# A1-A1_Switches_new.net
KiCad netlist of a schematic drawn in Altium Designer
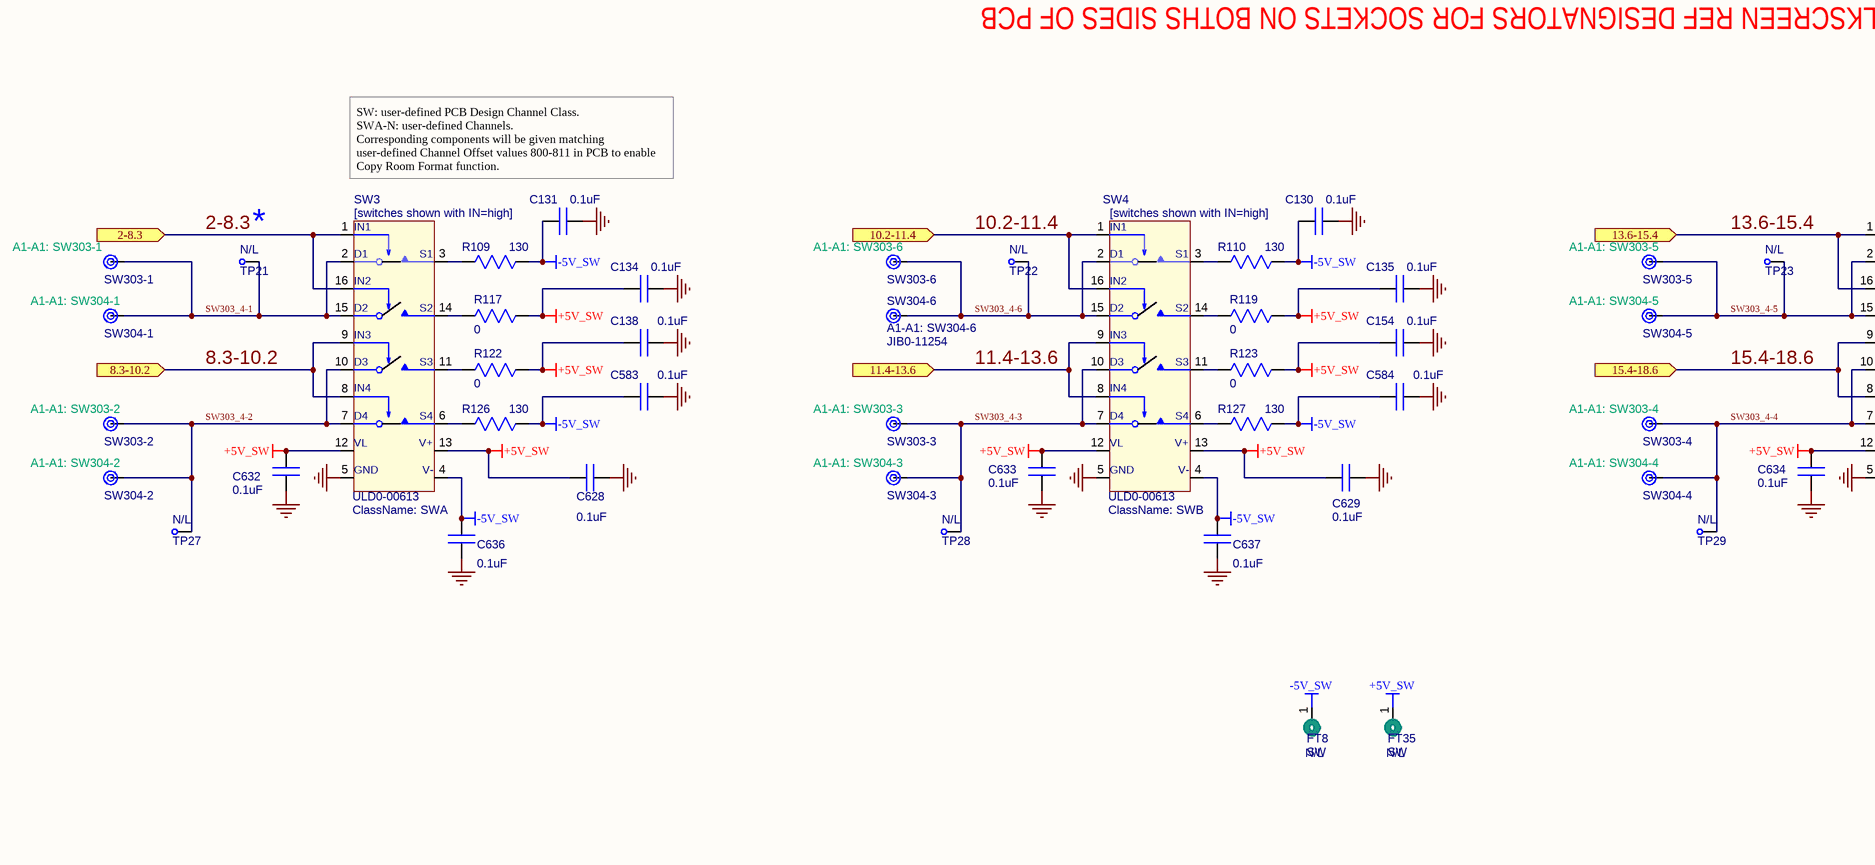
[diagram p0: A1-A1 Switches new.SchDoc, top left]
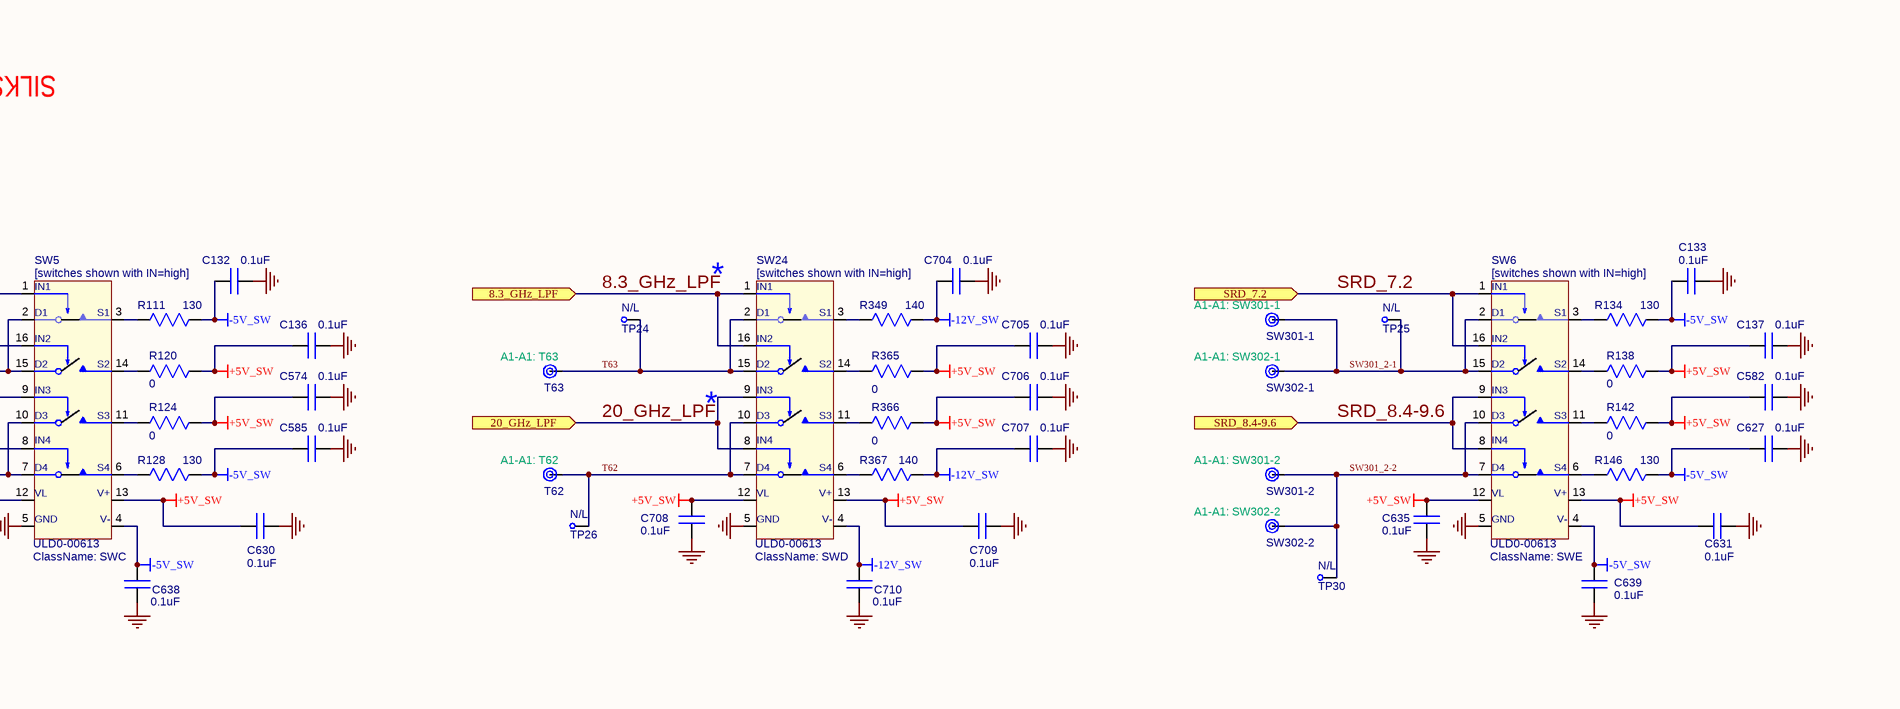
[diagram p1: A1-A1 Switches new.SchDoc, top right]
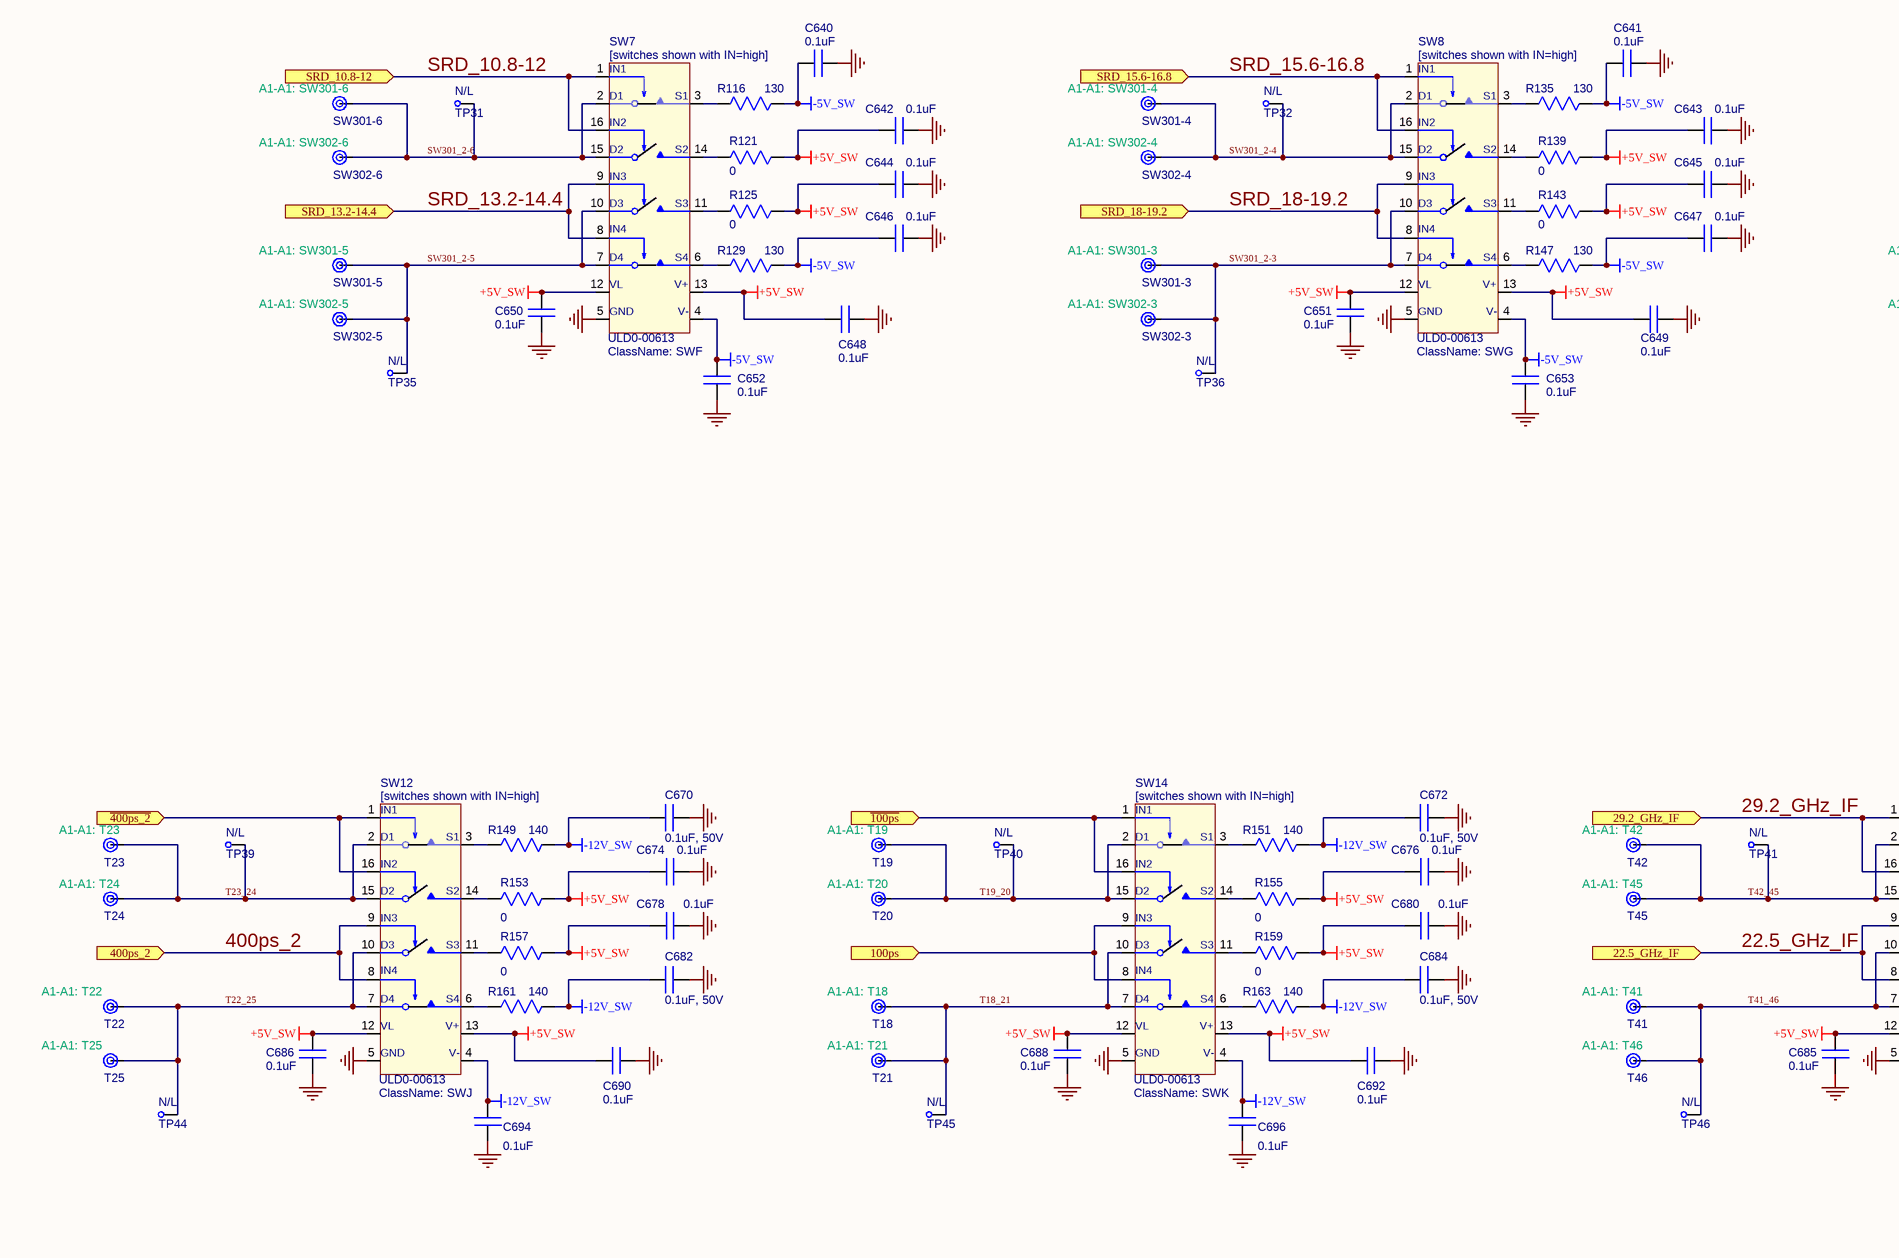
[diagram p2: A1-A1 Switches new.SchDoc, bottom left]
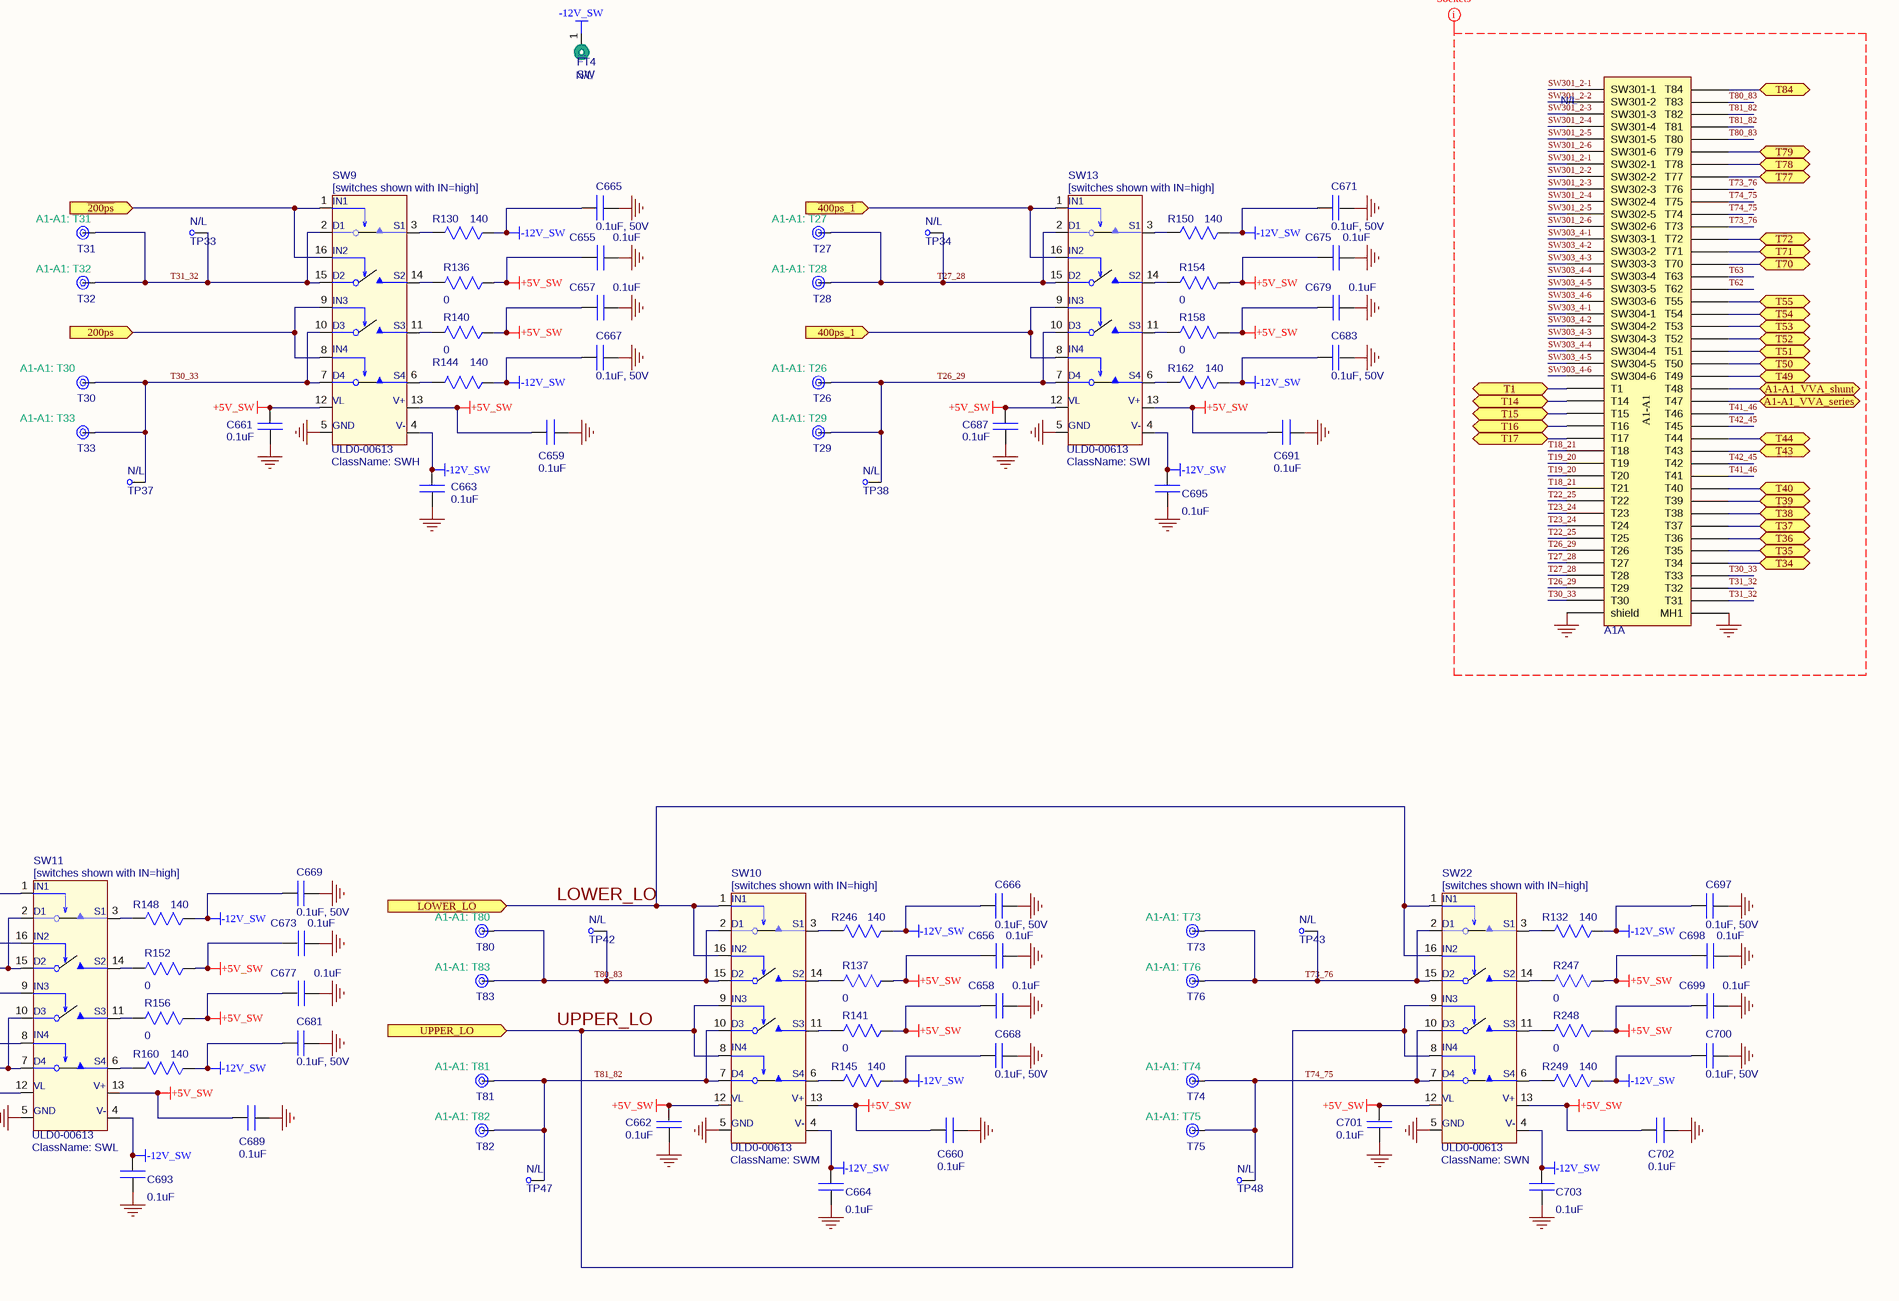
[diagram p3: A1-A1 Switches new.SchDoc, bottom right]

(export (version "E")
  (design (tool "Eeschema 10.0.6"))
  (components
    (comp (ref "A1")
      (value "PCB features")
      (footprint "Hydra_A1_output_modules")
      (description "Hydra A1 output modules (PCB features)")
      (fields (field (name "NOLOAD") "N/L") (field (name "APPROVED") "*"))
      (libsource (lib "Giga-tronics") (part "Hydra A1 output modules"))
    )
    (comp (ref "C130")
      (value "0.1uF")
      (footprint "CAP-0402-N")
      (description ".1 UF,10%;X7R;16V,CHIP;0402")
      (fields (field (name "APPROVED") "CL"))
      (libsource (lib "Giga-tronics") (part "CK40-04100"))
    )
    (comp (ref "C131")
      (value "0.1uF")
      (footprint "CAP-0402-N")
      (description ".1 UF,10%;X7R;16V,CHIP;0402")
      (fields (field (name "APPROVED") "CL"))
      (libsource (lib "Giga-tronics") (part "CK40-04100"))
    )
    (comp (ref "C132")
      (value "0.1uF")
      (footprint "CAP-0402-N")
      (description ".1 UF,10%;X7R;16V,CHIP;0402")
      (fields (field (name "APPROVED") "CL"))
      (libsource (lib "Giga-tronics") (part "CK40-04100"))
    )
    (comp (ref "C133")
      (value "0.1uF")
      (footprint "CAP-0402-N")
      (description ".1 UF,10%;X7R;16V,CHIP;0402")
      (fields (field (name "APPROVED") "CL"))
      (libsource (lib "Giga-tronics") (part "CK40-04100"))
    )
    (comp (ref "C134")
      (value "0.1uF")
      (footprint "CAP-0402-N")
      (description ".1 UF,10%;X7R;16V,CHIP;0402")
      (fields (field (name "APPROVED") "CL"))
      (libsource (lib "Giga-tronics") (part "CK40-04100"))
    )
    (comp (ref "C135")
      (value "0.1uF")
      (footprint "CAP-0402-N")
      (description ".1 UF,10%;X7R;16V,CHIP;0402")
      (fields (field (name "APPROVED") "CL"))
      (libsource (lib "Giga-tronics") (part "CK40-04100"))
    )
    (comp (ref "C136")
      (value "0.1uF")
      (footprint "CAP-0402-N")
      (description ".1 UF,10%;X7R;16V,CHIP;0402")
      (fields (field (name "APPROVED") "CL"))
      (libsource (lib "Giga-tronics") (part "CK40-04100"))
    )
    (comp (ref "C137")
      (value "0.1uF")
      (footprint "CAP-0402-N")
      (description ".1 UF,10%;X7R;16V,CHIP;0402")
      (fields (field (name "APPROVED") "CL"))
      (libsource (lib "Giga-tronics") (part "CK40-04100"))
    )
    (comp (ref "C138")
      (value "0.1uF")
      (footprint "CAP-0402-N")
      (description ".1 UF,10%;X7R;16V,CHIP;0402")
      (fields (field (name "APPROVED") "CL"))
      (libsource (lib "Giga-tronics") (part "CK40-04100"))
    )
    (comp (ref "C154")
      (value "0.1uF")
      (footprint "CAP-0402-N")
      (description ".1 UF,10%;X7R;16V,CHIP;0402")
      (fields (field (name "APPROVED") "CL"))
      (libsource (lib "Giga-tronics") (part "CK40-04100"))
    )
    (comp (ref "C574")
      (value "0.1uF")
      (footprint "CAP-0402-N")
      (description ".1 UF,10%;X7R;16V,CHIP;0402")
      (fields (field (name "APPROVED") "CL"))
      (libsource (lib "Giga-tronics") (part "CK40-04100"))
    )
    (comp (ref "C582")
      (value "0.1uF")
      (footprint "CAP-0402-N")
      (description ".1 UF,10%;X7R;16V,CHIP;0402")
      (fields (field (name "APPROVED") "CL"))
      (libsource (lib "Giga-tronics") (part "CK40-04100"))
    )
    (comp (ref "C583")
      (value "0.1uF")
      (footprint "CAP-0402-N")
      (description ".1 UF,10%;X7R;16V,CHIP;0402")
      (fields (field (name "APPROVED") "CL"))
      (libsource (lib "Giga-tronics") (part "CK40-04100"))
    )
    (comp (ref "C584")
      (value "0.1uF")
      (footprint "CAP-0402-N")
      (description ".1 UF,10%;X7R;16V,CHIP;0402")
      (fields (field (name "APPROVED") "CL"))
      (libsource (lib "Giga-tronics") (part "CK40-04100"))
    )
    (comp (ref "C585")
      (value "0.1uF")
      (footprint "CAP-0402-N")
      (description ".1 UF,10%;X7R;16V,CHIP;0402")
      (fields (field (name "APPROVED") "CL"))
      (libsource (lib "Giga-tronics") (part "CK40-04100"))
    )
    (comp (ref "C627")
      (value "0.1uF")
      (footprint "CAP-0402-N")
      (description ".1 UF,10%;X7R;16V,CHIP;0402")
      (fields (field (name "APPROVED") "CL"))
      (libsource (lib "Giga-tronics") (part "CK40-04100"))
    )
    (comp (ref "C628")
      (value "0.1uF")
      (footprint "CAP-0402-N")
      (description ".1 UF,10%;X7R;16V,CHIP;0402")
      (fields (field (name "APPROVED") "CL"))
      (libsource (lib "Giga-tronics") (part "CK40-04100"))
    )
    (comp (ref "C629")
      (value "0.1uF")
      (footprint "CAP-0402-N")
      (description ".1 UF,10%;X7R;16V,CHIP;0402")
      (fields (field (name "APPROVED") "CL"))
      (libsource (lib "Giga-tronics") (part "CK40-04100"))
    )
    (comp (ref "C630")
      (value "0.1uF")
      (footprint "CAP-0402-N")
      (description ".1 UF,10%;X7R;16V,CHIP;0402")
      (fields (field (name "APPROVED") "CL"))
      (libsource (lib "Giga-tronics") (part "CK40-04100"))
    )
    (comp (ref "C631")
      (value "0.1uF")
      (footprint "CAP-0402-N")
      (description ".1 UF,10%;X7R;16V,CHIP;0402")
      (fields (field (name "APPROVED") "CL"))
      (libsource (lib "Giga-tronics") (part "CK40-04100"))
    )
    (comp (ref "C632")
      (value "0.1uF")
      (footprint "CAP-0402-N")
      (description ".1 UF,10%;X7R;16V,CHIP;0402")
      (fields (field (name "APPROVED") "CL"))
      (libsource (lib "Giga-tronics") (part "CK40-04100"))
    )
    (comp (ref "C633")
      (value "0.1uF")
      (footprint "CAP-0402-N")
      (description ".1 UF,10%;X7R;16V,CHIP;0402")
      (fields (field (name "APPROVED") "CL"))
      (libsource (lib "Giga-tronics") (part "CK40-04100"))
    )
    (comp (ref "C634")
      (value "0.1uF")
      (footprint "CAP-0402-N")
      (description ".1 UF,10%;X7R;16V,CHIP;0402")
      (fields (field (name "APPROVED") "CL"))
      (libsource (lib "Giga-tronics") (part "CK40-04100"))
    )
    (comp (ref "C635")
      (value "0.1uF")
      (footprint "CAP-0402-N")
      (description ".1 UF,10%;X7R;16V,CHIP;0402")
      (fields (field (name "APPROVED") "CL"))
      (libsource (lib "Giga-tronics") (part "CK40-04100"))
    )
    (comp (ref "C636")
      (value "0.1uF")
      (footprint "CAP-0402-N")
      (description ".1 UF,10%;X7R;16V,CHIP;0402")
      (fields (field (name "APPROVED") "CL"))
      (libsource (lib "Giga-tronics") (part "CK40-04100"))
    )
    (comp (ref "C637")
      (value "0.1uF")
      (footprint "CAP-0402-N")
      (description ".1 UF,10%;X7R;16V,CHIP;0402")
      (fields (field (name "APPROVED") "CL"))
      (libsource (lib "Giga-tronics") (part "CK40-04100"))
    )
    (comp (ref "C638")
      (value "0.1uF")
      (footprint "CAP-0402-N")
      (description ".1 UF,10%;X7R;16V,CHIP;0402")
      (fields (field (name "APPROVED") "CL"))
      (libsource (lib "Giga-tronics") (part "CK40-04100"))
    )
    (comp (ref "C639")
      (value "0.1uF")
      (footprint "CAP-0402-N")
      (description ".1 UF,10%;X7R;16V,CHIP;0402")
      (fields (field (name "APPROVED") "CL"))
      (libsource (lib "Giga-tronics") (part "CK40-04100"))
    )
    (comp (ref "C640")
      (value "0.1uF")
      (footprint "CAP-0402-N")
      (description ".1 UF,10%;X7R;16V,CHIP;0402")
      (fields (field (name "APPROVED") "CL"))
      (libsource (lib "Giga-tronics") (part "CK40-04100"))
    )
    (comp (ref "C641")
      (value "0.1uF")
      (footprint "CAP-0402-N")
      (description ".1 UF,10%;X7R;16V,CHIP;0402")
      (fields (field (name "APPROVED") "CL"))
      (libsource (lib "Giga-tronics") (part "CK40-04100"))
    )
    (comp (ref "C642")
      (value "0.1uF")
      (footprint "CAP-0402-N")
      (description ".1 UF,10%;X7R;16V,CHIP;0402")
      (fields (field (name "APPROVED") "CL"))
      (libsource (lib "Giga-tronics") (part "CK40-04100"))
    )
    (comp (ref "C643")
      (value "0.1uF")
      (footprint "CAP-0402-N")
      (description ".1 UF,10%;X7R;16V,CHIP;0402")
      (fields (field (name "APPROVED") "CL"))
      (libsource (lib "Giga-tronics") (part "CK40-04100"))
    )
    (comp (ref "C644")
      (value "0.1uF")
      (footprint "CAP-0402-N")
      (description ".1 UF,10%;X7R;16V,CHIP;0402")
      (fields (field (name "APPROVED") "CL"))
      (libsource (lib "Giga-tronics") (part "CK40-04100"))
    )
    (comp (ref "C645")
      (value "0.1uF")
      (footprint "CAP-0402-N")
      (description ".1 UF,10%;X7R;16V,CHIP;0402")
      (fields (field (name "APPROVED") "CL"))
      (libsource (lib "Giga-tronics") (part "CK40-04100"))
    )
    (comp (ref "C646")
      (value "0.1uF")
      (footprint "CAP-0402-N")
      (description ".1 UF,10%;X7R;16V,CHIP;0402")
      (fields (field (name "APPROVED") "CL"))
      (libsource (lib "Giga-tronics") (part "CK40-04100"))
    )
    (comp (ref "C647")
      (value "0.1uF")
      (footprint "CAP-0402-N")
      (description ".1 UF,10%;X7R;16V,CHIP;0402")
      (fields (field (name "APPROVED") "CL"))
      (libsource (lib "Giga-tronics") (part "CK40-04100"))
    )
    (comp (ref "C648")
      (value "0.1uF")
      (footprint "CAP-0402-N")
      (description ".1 UF,10%;X7R;16V,CHIP;0402")
      (fields (field (name "APPROVED") "CL"))
      (libsource (lib "Giga-tronics") (part "CK40-04100"))
    )
    (comp (ref "C649")
      (value "0.1uF")
      (footprint "CAP-0402-N")
      (description ".1 UF,10%;X7R;16V,CHIP;0402")
      (fields (field (name "APPROVED") "CL"))
      (libsource (lib "Giga-tronics") (part "CK40-04100"))
    )
    (comp (ref "C650")
      (value "0.1uF")
      (footprint "CAP-0402-N")
      (description ".1 UF,10%;X7R;16V,CHIP;0402")
      (fields (field (name "APPROVED") "CL"))
      (libsource (lib "Giga-tronics") (part "CK40-04100"))
    )
    (comp (ref "C651")
      (value "0.1uF")
      (footprint "CAP-0402-N")
      (description ".1 UF,10%;X7R;16V,CHIP;0402")
      (fields (field (name "APPROVED") "CL"))
      (libsource (lib "Giga-tronics") (part "CK40-04100"))
    )
    (comp (ref "C652")
      (value "0.1uF")
      (footprint "CAP-0402-N")
      (description ".1 UF,10%;X7R;16V,CHIP;0402")
      (fields (field (name "APPROVED") "CL"))
      (libsource (lib "Giga-tronics") (part "CK40-04100"))
    )
    (comp (ref "C653")
      (value "0.1uF")
      (footprint "CAP-0402-N")
      (description ".1 UF,10%;X7R;16V,CHIP;0402")
      (fields (field (name "APPROVED") "CL"))
      (libsource (lib "Giga-tronics") (part "CK40-04100"))
    )
    (comp (ref "C655")
      (value "0.1uF")
      (footprint "CAP-0402-N")
      (description ".1 UF,10%;X7R;16V,CHIP;0402")
      (fields (field (name "APPROVED") "CL"))
      (libsource (lib "Giga-tronics") (part "CK40-04100"))
    )
    (comp (ref "C656")
      (value "0.1uF")
      (footprint "CAP-0402-N")
      (description ".1 UF,10%;X7R;16V,CHIP;0402")
      (fields (field (name "APPROVED") "CL"))
      (libsource (lib "Giga-tronics") (part "CK40-04100"))
    )
    (comp (ref "C657")
      (value "0.1uF")
      (footprint "CAP-0402-N")
      (description ".1 UF,10%;X7R;16V,CHIP;0402")
      (fields (field (name "APPROVED") "CL"))
      (libsource (lib "Giga-tronics") (part "CK40-04100"))
    )
    (comp (ref "C658")
      (value "0.1uF")
      (footprint "CAP-0402-N")
      (description ".1 UF,10%;X7R;16V,CHIP;0402")
      (fields (field (name "APPROVED") "CL"))
      (libsource (lib "Giga-tronics") (part "CK40-04100"))
    )
    (comp (ref "C659")
      (value "0.1uF")
      (footprint "CAP-0402-N")
      (description ".1 UF,10%;X7R;16V,CHIP;0402")
      (fields (field (name "APPROVED") "CL"))
      (libsource (lib "Giga-tronics") (part "CK40-04100"))
    )
    (comp (ref "C660")
      (value "0.1uF")
      (footprint "CAP-0402-N")
      (description ".1 UF,10%;X7R;16V,CHIP;0402")
      (fields (field (name "APPROVED") "CL"))
      (libsource (lib "Giga-tronics") (part "CK40-04100"))
    )
    (comp (ref "C661")
      (value "0.1uF")
      (footprint "CAP-0402-N")
      (description ".1 UF,10%;X7R;16V,CHIP;0402")
      (fields (field (name "APPROVED") "CL"))
      (libsource (lib "Giga-tronics") (part "CK40-04100"))
    )
    (comp (ref "C662")
      (value "0.1uF")
      (footprint "CAP-0402-N")
      (description ".1 UF,10%;X7R;16V,CHIP;0402")
      (fields (field (name "APPROVED") "CL"))
      (libsource (lib "Giga-tronics") (part "CK40-04100"))
    )
    (comp (ref "C663")
      (value "0.1uF")
      (footprint "CAP-0402-N")
      (description ".1 UF,10%;X7R;16V,CHIP;0402")
      (fields (field (name "APPROVED") "CL"))
      (libsource (lib "Giga-tronics") (part "CK40-04100"))
    )
    (comp (ref "C664")
      (value "0.1uF")
      (footprint "CAP-0402-N")
      (description ".1 UF,10%;X7R;16V,CHIP;0402")
      (fields (field (name "APPROVED") "CL"))
      (libsource (lib "Giga-tronics") (part "CK40-04100"))
    )
    (comp (ref "C665")
      (value "0.1uF, 50V")
      (footprint "CAP-0603-N")
      (description ".1UF;5%;X7R;50V;CHIP;0603")
      (fields (field (name "APPROVED") "CL"))
      (libsource (lib "Giga-tronics") (part "CK45-14100"))
    )
    (comp (ref "C666")
      (value "0.1uF, 50V")
      (footprint "CAP-0603-N")
      (description ".1UF;5%;X7R;50V;CHIP;0603")
      (fields (field (name "APPROVED") "CL"))
      (libsource (lib "Giga-tronics") (part "CK45-14100"))
    )
    (comp (ref "C667")
      (value "0.1uF, 50V")
      (footprint "CAP-0603-N")
      (description ".1UF;5%;X7R;50V;CHIP;0603")
      (fields (field (name "APPROVED") "CL"))
      (libsource (lib "Giga-tronics") (part "CK45-14100"))
    )
    (comp (ref "C668")
      (value "0.1uF, 50V")
      (footprint "CAP-0603-N")
      (description ".1UF;5%;X7R;50V;CHIP;0603")
      (fields (field (name "APPROVED") "CL"))
      (libsource (lib "Giga-tronics") (part "CK45-14100"))
    )
    (comp (ref "C669")
      (value "0.1uF, 50V")
      (footprint "CAP-0603-N")
      (description ".1UF;5%;X7R;50V;CHIP;0603")
      (fields (field (name "APPROVED") "CL"))
      (libsource (lib "Giga-tronics") (part "CK45-14100"))
    )
    (comp (ref "C670")
      (value "0.1uF, 50V")
      (footprint "CAP-0603-N")
      (description ".1UF;5%;X7R;50V;CHIP;0603")
      (fields (field (name "APPROVED") "CL"))
      (libsource (lib "Giga-tronics") (part "CK45-14100"))
    )
    (comp (ref "C671")
      (value "0.1uF, 50V")
      (footprint "CAP-0603-N")
      (description ".1UF;5%;X7R;50V;CHIP;0603")
      (fields (field (name "APPROVED") "CL"))
      (libsource (lib "Giga-tronics") (part "CK45-14100"))
    )
    (comp (ref "C672")
      (value "0.1uF, 50V")
      (footprint "CAP-0603-N")
      (description ".1UF;5%;X7R;50V;CHIP;0603")
      (fields (field (name "APPROVED") "CL"))
      (libsource (lib "Giga-tronics") (part "CK45-14100"))
    )
    (comp (ref "C673")
      (value "0.1uF")
      (footprint "CAP-0402-N")
      (description ".1 UF,10%;X7R;16V,CHIP;0402")
      (fields (field (name "APPROVED") "CL"))
      (libsource (lib "Giga-tronics") (part "CK40-04100"))
    )
    (comp (ref "C674")
      (value "0.1uF")
      (footprint "CAP-0402-N")
      (description ".1 UF,10%;X7R;16V,CHIP;0402")
      (fields (field (name "APPROVED") "CL"))
      (libsource (lib "Giga-tronics") (part "CK40-04100"))
    )
    (comp (ref "C675")
      (value "0.1uF")
      (footprint "CAP-0402-N")
      (description ".1 UF,10%;X7R;16V,CHIP;0402")
      (fields (field (name "APPROVED") "CL"))
      (libsource (lib "Giga-tronics") (part "CK40-04100"))
    )
    (comp (ref "C676")
      (value "0.1uF")
      (footprint "CAP-0402-N")
      (description ".1 UF,10%;X7R;16V,CHIP;0402")
      (fields (field (name "APPROVED") "CL"))
      (libsource (lib "Giga-tronics") (part "CK40-04100"))
    )
    (comp (ref "C677")
      (value "0.1uF")
      (footprint "CAP-0402-N")
      (description ".1 UF,10%;X7R;16V,CHIP;0402")
      (fields (field (name "APPROVED") "CL"))
      (libsource (lib "Giga-tronics") (part "CK40-04100"))
    )
    (comp (ref "C678")
      (value "0.1uF")
      (footprint "CAP-0402-N")
      (description ".1 UF,10%;X7R;16V,CHIP;0402")
      (fields (field (name "APPROVED") "CL"))
      (libsource (lib "Giga-tronics") (part "CK40-04100"))
    )
    (comp (ref "C679")
      (value "0.1uF")
      (footprint "CAP-0402-N")
      (description ".1 UF,10%;X7R;16V,CHIP;0402")
      (fields (field (name "APPROVED") "CL"))
      (libsource (lib "Giga-tronics") (part "CK40-04100"))
    )
    (comp (ref "C680")
      (value "0.1uF")
      (footprint "CAP-0402-N")
      (description ".1 UF,10%;X7R;16V,CHIP;0402")
      (fields (field (name "APPROVED") "CL"))
      (libsource (lib "Giga-tronics") (part "CK40-04100"))
    )
    (comp (ref "C681")
      (value "0.1uF, 50V")
      (footprint "CAP-0603-N")
      (description ".1UF;5%;X7R;50V;CHIP;0603")
      (fields (field (name "APPROVED") "CL"))
      (libsource (lib "Giga-tronics") (part "CK45-14100"))
    )
    (comp (ref "C682")
      (value "0.1uF, 50V")
      (footprint "CAP-0603-N")
      (description ".1UF;5%;X7R;50V;CHIP;0603")
      (fields (field (name "APPROVED") "CL"))
      (libsource (lib "Giga-tronics") (part "CK45-14100"))
    )
    (comp (ref "C683")
      (value "0.1uF, 50V")
      (footprint "CAP-0603-N")
      (description ".1UF;5%;X7R;50V;CHIP;0603")
      (fields (field (name "APPROVED") "CL"))
      (libsource (lib "Giga-tronics") (part "CK45-14100"))
    )
    (comp (ref "C684")
      (value "0.1uF, 50V")
      (footprint "CAP-0603-N")
      (description ".1UF;5%;X7R;50V;CHIP;0603")
      (fields (field (name "APPROVED") "CL"))
      (libsource (lib "Giga-tronics") (part "CK45-14100"))
    )
    (comp (ref "C685")
      (value "0.1uF")
      (footprint "CAP-0402-N")
      (description ".1 UF,10%;X7R;16V,CHIP;0402")
      (fields (field (name "APPROVED") "CL"))
      (libsource (lib "Giga-tronics") (part "CK40-04100"))
    )
    (comp (ref "C686")
      (value "0.1uF")
      (footprint "CAP-0402-N")
      (description ".1 UF,10%;X7R;16V,CHIP;0402")
      (fields (field (name "APPROVED") "CL"))
      (libsource (lib "Giga-tronics") (part "CK40-04100"))
    )
    (comp (ref "C687")
      (value "0.1uF")
      (footprint "CAP-0402-N")
      (description ".1 UF,10%;X7R;16V,CHIP;0402")
      (fields (field (name "APPROVED") "CL"))
      (libsource (lib "Giga-tronics") (part "CK40-04100"))
    )
    (comp (ref "C688")
      (value "0.1uF")
      (footprint "CAP-0402-N")
      (description ".1 UF,10%;X7R;16V,CHIP;0402")
      (fields (field (name "APPROVED") "CL"))
      (libsource (lib "Giga-tronics") (part "CK40-04100"))
    )
    (comp (ref "C689")
      (value "0.1uF")
      (footprint "CAP-0402-N")
      (description ".1 UF,10%;X7R;16V,CHIP;0402")
      (fields (field (name "APPROVED") "CL"))
      (libsource (lib "Giga-tronics") (part "CK40-04100"))
    )
    (comp (ref "C690")
      (value "0.1uF")
      (footprint "CAP-0402-N")
      (description ".1 UF,10%;X7R;16V,CHIP;0402")
      (fields (field (name "APPROVED") "CL"))
      (libsource (lib "Giga-tronics") (part "CK40-04100"))
    )
    (comp (ref "C691")
      (value "0.1uF")
      (footprint "CAP-0402-N")
      (description ".1 UF,10%;X7R;16V,CHIP;0402")
      (fields (field (name "APPROVED") "CL"))
      (libsource (lib "Giga-tronics") (part "CK40-04100"))
    )
    (comp (ref "C692")
      (value "0.1uF")
      (footprint "CAP-0402-N")
      (description ".1 UF,10%;X7R;16V,CHIP;0402")
      (fields (field (name "APPROVED") "CL"))
      (libsource (lib "Giga-tronics") (part "CK40-04100"))
    )
    (comp (ref "C693")
      (value "0.1uF")
      (footprint "CAP-0402-N")
      (description ".1 UF,10%;X7R;16V,CHIP;0402")
      (fields (field (name "APPROVED") "CL"))
      (libsource (lib "Giga-tronics") (part "CK40-04100"))
    )
    (comp (ref "C694")
      (value "0.1uF")
      (footprint "CAP-0402-N")
      (description ".1 UF,10%;X7R;16V,CHIP;0402")
      (fields (field (name "APPROVED") "CL"))
      (libsource (lib "Giga-tronics") (part "CK40-04100"))
    )
    (comp (ref "C695")
      (value "0.1uF")
      (footprint "CAP-0402-N")
      (description ".1 UF,10%;X7R;16V,CHIP;0402")
      (fields (field (name "APPROVED") "CL"))
      (libsource (lib "Giga-tronics") (part "CK40-04100"))
    )
    (comp (ref "C696")
      (value "0.1uF")
      (footprint "CAP-0402-N")
      (description ".1 UF,10%;X7R;16V,CHIP;0402")
      (fields (field (name "APPROVED") "CL"))
      (libsource (lib "Giga-tronics") (part "CK40-04100"))
    )
    (comp (ref "C697")
      (value "0.1uF, 50V")
      (footprint "CAP-0603-N")
      (description ".1UF;5%;X7R;50V;CHIP;0603")
      (fields (field (name "APPROVED") "CL"))
      (libsource (lib "Giga-tronics") (part "CK45-14100"))
    )
    (comp (ref "C698")
      (value "0.1uF")
      (footprint "CAP-0402-N")
      (description ".1 UF,10%;X7R;16V,CHIP;0402")
      (fields (field (name "APPROVED") "CL"))
      (libsource (lib "Giga-tronics") (part "CK40-04100"))
    )
    (comp (ref "C699")
      (value "0.1uF")
      (footprint "CAP-0402-N")
      (description ".1 UF,10%;X7R;16V,CHIP;0402")
      (fields (field (name "APPROVED") "CL"))
      (libsource (lib "Giga-tronics") (part "CK40-04100"))
    )
    (comp (ref "C700")
      (value "0.1uF, 50V")
      (footprint "CAP-0603-N")
      (description ".1UF;5%;X7R;50V;CHIP;0603")
      (fields (field (name "APPROVED") "CL"))
      (libsource (lib "Giga-tronics") (part "CK45-14100"))
    )
    (comp (ref "C701")
      (value "0.1uF")
      (footprint "CAP-0402-N")
      (description ".1 UF,10%;X7R;16V,CHIP;0402")
      (fields (field (name "APPROVED") "CL"))
      (libsource (lib "Giga-tronics") (part "CK40-04100"))
    )
    (comp (ref "C702")
      (value "0.1uF")
      (footprint "CAP-0402-N")
      (description ".1 UF,10%;X7R;16V,CHIP;0402")
      (fields (field (name "APPROVED") "CL"))
      (libsource (lib "Giga-tronics") (part "CK40-04100"))
    )
    (comp (ref "C703")
      (value "0.1uF")
      (footprint "CAP-0402-N")
      (description ".1 UF,10%;X7R;16V,CHIP;0402")
      (fields (field (name "APPROVED") "CL"))
      (libsource (lib "Giga-tronics") (part "CK40-04100"))
    )
    (comp (ref "C704")
      (value "0.1uF")
      (footprint "CAP-0402-N")
      (description ".1 UF,10%;X7R;16V,CHIP;0402")
      (fields (field (name "APPROVED") "CL"))
      (libsource (lib "Giga-tronics") (part "CK40-04100"))
    )
    (comp (ref "C705")
      (value "0.1uF")
      (footprint "CAP-0402-N")
      (description ".1 UF,10%;X7R;16V,CHIP;0402")
      (fields (field (name "APPROVED") "CL"))
      (libsource (lib "Giga-tronics") (part "CK40-04100"))
    )
    (comp (ref "C706")
      (value "0.1uF")
      (footprint "CAP-0402-N")
      (description ".1 UF,10%;X7R;16V,CHIP;0402")
      (fields (field (name "APPROVED") "CL"))
      (libsource (lib "Giga-tronics") (part "CK40-04100"))
    )
    (comp (ref "C707")
      (value "0.1uF")
      (footprint "CAP-0402-N")
      (description ".1 UF,10%;X7R;16V,CHIP;0402")
      (fields (field (name "APPROVED") "CL"))
      (libsource (lib "Giga-tronics") (part "CK40-04100"))
    )
    (comp (ref "C708")
      (value "0.1uF")
      (footprint "CAP-0402-N")
      (description ".1 UF,10%;X7R;16V,CHIP;0402")
      (fields (field (name "APPROVED") "CL"))
      (libsource (lib "Giga-tronics") (part "CK40-04100"))
    )
    (comp (ref "C709")
      (value "0.1uF")
      (footprint "CAP-0402-N")
      (description ".1 UF,10%;X7R;16V,CHIP;0402")
      (fields (field (name "APPROVED") "CL"))
      (libsource (lib "Giga-tronics") (part "CK40-04100"))
    )
    (comp (ref "C710")
      (value "0.1uF")
      (footprint "CAP-0402-N")
      (description ".1 UF,10%;X7R;16V,CHIP;0402")
      (fields (field (name "APPROVED") "CL"))
      (libsource (lib "Giga-tronics") (part "CK40-04100"))
    )
    (comp (ref "FT4")
      (value "SW")
      (footprint "FromToNode_ML2")
      (fields (field (name "NOLOAD") "N/L") (field (name "APPROVED") "*"))
      (libsource (lib "Giga-tronics") (part "FromToNode"))
    )
    (comp (ref "FT8")
      (value "SW")
      (footprint "FromToNode_ML2")
      (fields (field (name "NOLOAD") "N/L") (field (name "APPROVED") "*"))
      (libsource (lib "Giga-tronics") (part "FromToNode"))
    )
    (comp (ref "FT35")
      (value "SW")
      (footprint "FromToNode_ML2")
      (fields (field (name "NOLOAD") "N/L") (field (name "APPROVED") "*"))
      (libsource (lib "Giga-tronics") (part "FromToNode"))
    )
    (comp (ref "R109")
      (value "130")
      (footprint "RES-0603-N")
      (description "130 OHMS;.1W;1%;200PPM;FILM;CHIP;0603")
      (fields (field (name "APPROVED") "CL"))
      (libsource (lib "Giga-tronics") (part "RK40-01300"))
    )
    (comp (ref "R110")
      (value "130")
      (footprint "RES-0603-N")
      (description "130 OHMS;.1W;1%;200PPM;FILM;CHIP;0603")
      (fields (field (name "APPROVED") "CL"))
      (libsource (lib "Giga-tronics") (part "RK40-01300"))
    )
    (comp (ref "R111")
      (value "130")
      (footprint "RES-0603-N")
      (description "130 OHMS;.1W;1%;200PPM;FILM;CHIP;0603")
      (fields (field (name "APPROVED") "CL"))
      (libsource (lib "Giga-tronics") (part "RK40-01300"))
    )
    (comp (ref "R116")
      (value "130")
      (footprint "RES-0603-N")
      (description "130 OHMS;.1W;1%;200PPM;FILM;CHIP;0603")
      (fields (field (name "APPROVED") "CL"))
      (libsource (lib "Giga-tronics") (part "RK40-01300"))
    )
    (comp (ref "R117")
      (value "0")
      (footprint "RES-0603-N")
      (description "JUMPER;.05 OHMS MAX;1A MAX;0603")
      (fields (field (name "APPROVED") "CL"))
      (libsource (lib "Giga-tronics") (part "RK40-00000"))
    )
    (comp (ref "R119")
      (value "0")
      (footprint "RES-0603-N")
      (description "JUMPER;.05 OHMS MAX;1A MAX;0603")
      (fields (field (name "APPROVED") "CL"))
      (libsource (lib "Giga-tronics") (part "RK40-00000"))
    )
    (comp (ref "R120")
      (value "0")
      (footprint "RES-0603-N")
      (description "JUMPER;.05 OHMS MAX;1A MAX;0603")
      (fields (field (name "APPROVED") "CL"))
      (libsource (lib "Giga-tronics") (part "RK40-00000"))
    )
    (comp (ref "R121")
      (value "0")
      (footprint "RES-0603-N")
      (description "JUMPER;.05 OHMS MAX;1A MAX;0603")
      (fields (field (name "APPROVED") "CL"))
      (libsource (lib "Giga-tronics") (part "RK40-00000"))
    )
    (comp (ref "R122")
      (value "0")
      (footprint "RES-0603-N")
      (description "JUMPER;.05 OHMS MAX;1A MAX;0603")
      (fields (field (name "APPROVED") "CL"))
      (libsource (lib "Giga-tronics") (part "RK40-00000"))
    )
    (comp (ref "R123")
      (value "0")
      (footprint "RES-0603-N")
      (description "JUMPER;.05 OHMS MAX;1A MAX;0603")
      (fields (field (name "APPROVED") "CL"))
      (libsource (lib "Giga-tronics") (part "RK40-00000"))
    )
    (comp (ref "R124")
      (value "0")
      (footprint "RES-0603-N")
      (description "JUMPER;.05 OHMS MAX;1A MAX;0603")
      (fields (field (name "APPROVED") "CL"))
      (libsource (lib "Giga-tronics") (part "RK40-00000"))
    )
    (comp (ref "R125")
      (value "0")
      (footprint "RES-0603-N")
      (description "JUMPER;.05 OHMS MAX;1A MAX;0603")
      (fields (field (name "APPROVED") "CL"))
      (libsource (lib "Giga-tronics") (part "RK40-00000"))
    )
    (comp (ref "R126")
      (value "130")
      (footprint "RES-0603-N")
      (description "130 OHMS;.1W;1%;200PPM;FILM;CHIP;0603")
      (fields (field (name "APPROVED") "CL"))
      (libsource (lib "Giga-tronics") (part "RK40-01300"))
    )
    (comp (ref "R127")
      (value "130")
      (footprint "RES-0603-N")
      (description "130 OHMS;.1W;1%;200PPM;FILM;CHIP;0603")
      (fields (field (name "APPROVED") "CL"))
      (libsource (lib "Giga-tronics") (part "RK40-01300"))
    )
    (comp (ref "R128")
      (value "130")
      (footprint "RES-0603-N")
      (description "130 OHMS;.1W;1%;200PPM;FILM;CHIP;0603")
      (fields (field (name "APPROVED") "CL"))
      (libsource (lib "Giga-tronics") (part "RK40-01300"))
    )
    (comp (ref "R129")
      (value "130")
      (footprint "RES-0603-N")
      (description "130 OHMS;.1W;1%;200PPM;FILM;CHIP;0603")
      (fields (field (name "APPROVED") "CL"))
      (libsource (lib "Giga-tronics") (part "RK40-01300"))
    )
    (comp (ref "R130")
      (value "140")
      (footprint "RES-0603-N")
      (description "140 OHMS;.1W;1%;200PPM;FILM;CHIP;0603")
      (fields (field (name "APPROVED") "CL"))
      (libsource (lib "Giga-tronics") (part "RK41-01400"))
    )
    (comp (ref "R132")
      (value "140")
      (footprint "RES-0402-N")
      (description "140 OHMS; 1%; .1W; 100PPM; FILM; CHIP; 0402")
      (fields (field (name "APPROVED") "CL"))
      (libsource (lib "Giga-tronics") (part "RK35-01400"))
    )
    (comp (ref "R134")
      (value "130")
      (footprint "RES-0603-N")
      (description "130 OHMS;.1W;1%;200PPM;FILM;CHIP;0603")
      (fields (field (name "APPROVED") "CL"))
      (libsource (lib "Giga-tronics") (part "RK40-01300"))
    )
    (comp (ref "R135")
      (value "130")
      (footprint "RES-0603-N")
      (description "130 OHMS;.1W;1%;200PPM;FILM;CHIP;0603")
      (fields (field (name "APPROVED") "CL"))
      (libsource (lib "Giga-tronics") (part "RK40-01300"))
    )
    (comp (ref "R136")
      (value "0")
      (footprint "RES-0402-N")
      (description "JUMPER;0 OHMS;SMT;0402")
      (fields (field (name "APPROVED") "CL"))
      (libsource (lib "Giga-tronics") (part "RK35-00000"))
    )
    (comp (ref "R137")
      (value "0")
      (footprint "RES-0402-N")
      (description "JUMPER;0 OHMS;SMT;0402")
      (fields (field (name "APPROVED") "CL"))
      (libsource (lib "Giga-tronics") (part "RK35-00000"))
    )
    (comp (ref "R138")
      (value "0")
      (footprint "RES-0603-N")
      (description "JUMPER;.05 OHMS MAX;1A MAX;0603")
      (fields (field (name "APPROVED") "CL"))
      (libsource (lib "Giga-tronics") (part "RK40-00000"))
    )
    (comp (ref "R139")
      (value "0")
      (footprint "RES-0603-N")
      (description "JUMPER;.05 OHMS MAX;1A MAX;0603")
      (fields (field (name "APPROVED") "CL"))
      (libsource (lib "Giga-tronics") (part "RK40-00000"))
    )
    (comp (ref "R140")
      (value "0")
      (footprint "RES-0402-N")
      (description "JUMPER;0 OHMS;SMT;0402")
      (fields (field (name "APPROVED") "CL"))
      (libsource (lib "Giga-tronics") (part "RK35-00000"))
    )
    (comp (ref "R141")
      (value "0")
      (footprint "RES-0402-N")
      (description "JUMPER;0 OHMS;SMT;0402")
      (fields (field (name "APPROVED") "CL"))
      (libsource (lib "Giga-tronics") (part "RK35-00000"))
    )
    (comp (ref "R142")
      (value "0")
      (footprint "RES-0603-N")
      (description "JUMPER;.05 OHMS MAX;1A MAX;0603")
      (fields (field (name "APPROVED") "CL"))
      (libsource (lib "Giga-tronics") (part "RK40-00000"))
    )
    (comp (ref "R143")
      (value "0")
      (footprint "RES-0603-N")
      (description "JUMPER;.05 OHMS MAX;1A MAX;0603")
      (fields (field (name "APPROVED") "CL"))
      (libsource (lib "Giga-tronics") (part "RK40-00000"))
    )
    (comp (ref "R144")
      (value "140")
      (footprint "RES-0603-N")
      (description "140 OHMS;.1W;1%;200PPM;FILM;CHIP;0603")
      (fields (field (name "APPROVED") "CL"))
      (libsource (lib "Giga-tronics") (part "RK41-01400"))
    )
    (comp (ref "R145")
      (value "140")
      (footprint "RES-0402-N")
      (description "140 OHMS; 1%; .1W; 100PPM; FILM; CHIP; 0402")
      (fields (field (name "APPROVED") "CL"))
      (libsource (lib "Giga-tronics") (part "RK35-01400"))
    )
    (comp (ref "R146")
      (value "130")
      (footprint "RES-0603-N")
      (description "130 OHMS;.1W;1%;200PPM;FILM;CHIP;0603")
      (fields (field (name "APPROVED") "CL"))
      (libsource (lib "Giga-tronics") (part "RK40-01300"))
    )
    (comp (ref "R147")
      (value "130")
      (footprint "RES-0603-N")
      (description "130 OHMS;.1W;1%;200PPM;FILM;CHIP;0603")
      (fields (field (name "APPROVED") "CL"))
      (libsource (lib "Giga-tronics") (part "RK40-01300"))
    )
    (comp (ref "R148")
      (value "140")
      (footprint "RES-0603-N")
      (description "140 OHMS;.1W;1%;200PPM;FILM;CHIP;0603")
      (fields (field (name "APPROVED") "CL"))
      (libsource (lib "Giga-tronics") (part "RK41-01400"))
    )
    (comp (ref "R149")
      (value "140")
      (footprint "RES-0603-N")
      (description "140 OHMS;.1W;1%;200PPM;FILM;CHIP;0603")
      (fields (field (name "APPROVED") "CL"))
      (libsource (lib "Giga-tronics") (part "RK41-01400"))
    )
    (comp (ref "R150")
      (value "140")
      (footprint "RES-0603-N")
      (description "140 OHMS;.1W;1%;200PPM;FILM;CHIP;0603")
      (fields (field (name "APPROVED") "CL"))
      (libsource (lib "Giga-tronics") (part "RK41-01400"))
    )
    (comp (ref "R151")
      (value "140")
      (footprint "RES-0603-N")
      (description "140 OHMS;.1W;1%;200PPM;FILM;CHIP;0603")
      (fields (field (name "APPROVED") "CL"))
      (libsource (lib "Giga-tronics") (part "RK41-01400"))
    )
    (comp (ref "R152")
      (value "0")
      (footprint "RES-0402-N")
      (description "JUMPER;0 OHMS;SMT;0402")
      (fields (field (name "APPROVED") "CL"))
      (libsource (lib "Giga-tronics") (part "RK35-00000"))
    )
    (comp (ref "R153")
      (value "0")
      (footprint "RES-0402-N")
      (description "JUMPER;0 OHMS;SMT;0402")
      (fields (field (name "APPROVED") "CL"))
      (libsource (lib "Giga-tronics") (part "RK35-00000"))
    )
    (comp (ref "R154")
      (value "0")
      (footprint "RES-0402-N")
      (description "JUMPER;0 OHMS;SMT;0402")
      (fields (field (name "APPROVED") "CL"))
      (libsource (lib "Giga-tronics") (part "RK35-00000"))
    )
    (comp (ref "R155")
      (value "0")
      (footprint "RES-0402-N")
      (description "JUMPER;0 OHMS;SMT;0402")
      (fields (field (name "APPROVED") "CL"))
      (libsource (lib "Giga-tronics") (part "RK35-00000"))
    )
    (comp (ref "R156")
      (value "0")
      (footprint "RES-0402-N")
      (description "JUMPER;0 OHMS;SMT;0402")
      (fields (field (name "APPROVED") "CL"))
      (libsource (lib "Giga-tronics") (part "RK35-00000"))
    )
    (comp (ref "R157")
      (value "0")
      (footprint "RES-0402-N")
      (description "JUMPER;0 OHMS;SMT;0402")
      (fields (field (name "APPROVED") "CL"))
      (libsource (lib "Giga-tronics") (part "RK35-00000"))
    )
    (comp (ref "R158")
      (value "0")
      (footprint "RES-0402-N")
      (description "JUMPER;0 OHMS;SMT;0402")
      (fields (field (name "APPROVED") "CL"))
      (libsource (lib "Giga-tronics") (part "RK35-00000"))
    )
    (comp (ref "R159")
      (value "0")
      (footprint "RES-0402-N")
      (description "JUMPER;0 OHMS;SMT;0402")
      (fields (field (name "APPROVED") "CL"))
      (libsource (lib "Giga-tronics") (part "RK35-00000"))
    )
    (comp (ref "R160")
      (value "140")
      (footprint "RES-0603-N")
      (description "140 OHMS;.1W;1%;200PPM;FILM;CHIP;0603")
      (fields (field (name "APPROVED") "CL"))
      (libsource (lib "Giga-tronics") (part "RK41-01400"))
    )
    (comp (ref "R161")
      (value "140")
      (footprint "RES-0603-N")
      (description "140 OHMS;.1W;1%;200PPM;FILM;CHIP;0603")
      (fields (field (name "APPROVED") "CL"))
      (libsource (lib "Giga-tronics") (part "RK41-01400"))
    )
    (comp (ref "R162")
      (value "140")
      (footprint "RES-0603-N")
      (description "140 OHMS;.1W;1%;200PPM;FILM;CHIP;0603")
      (fields (field (name "APPROVED") "CL"))
      (libsource (lib "Giga-tronics") (part "RK41-01400"))
    )
    (comp (ref "R163")
      (value "140")
      (footprint "RES-0603-N")
      (description "140 OHMS;.1W;1%;200PPM;FILM;CHIP;0603")
      (fields (field (name "APPROVED") "CL"))
      (libsource (lib "Giga-tronics") (part "RK41-01400"))
    )
    (comp (ref "R246")
      (value "140")
      (footprint "RES-0402-N")
      (description "140 OHMS; 1%; .1W; 100PPM; FILM; CHIP; 0402")
      (fields (field (name "APPROVED") "CL"))
      (libsource (lib "Giga-tronics") (part "RK35-01400"))
    )
    (comp (ref "R247")
      (value "0")
      (footprint "RES-0402-N")
      (description "JUMPER;0 OHMS;SMT;0402")
      (fields (field (name "APPROVED") "CL"))
      (libsource (lib "Giga-tronics") (part "RK35-00000"))
    )
    (comp (ref "R248")
      (value "0")
      (footprint "RES-0402-N")
      (description "JUMPER;0 OHMS;SMT;0402")
      (fields (field (name "APPROVED") "CL"))
      (libsource (lib "Giga-tronics") (part "RK35-00000"))
    )
    (comp (ref "R249")
      (value "140")
      (footprint "RES-0402-N")
      (description "140 OHMS; 1%; .1W; 100PPM; FILM; CHIP; 0402")
      (fields (field (name "APPROVED") "CL"))
      (libsource (lib "Giga-tronics") (part "RK35-01400"))
    )
    (comp (ref "R349")
      (value "140")
      (footprint "RES-0402-N")
      (description "140 OHMS; 1%; .1W; 100PPM; FILM; CHIP; 0402")
      (fields (field (name "APPROVED") "CL"))
      (libsource (lib "Giga-tronics") (part "RK35-01400"))
    )
    (comp (ref "R365")
      (value "0")
      (footprint "RES-0402-N")
      (description "JUMPER;0 OHMS;SMT;0402")
      (fields (field (name "APPROVED") "CL"))
      (libsource (lib "Giga-tronics") (part "RK35-00000"))
    )
    (comp (ref "R366")
      (value "0")
      (footprint "RES-0402-N")
      (description "JUMPER;0 OHMS;SMT;0402")
      (fields (field (name "APPROVED") "CL"))
      (libsource (lib "Giga-tronics") (part "RK35-00000"))
    )
    (comp (ref "R367")
      (value "140")
      (footprint "RES-0402-N")
      (description "140 OHMS; 1%; .1W; 100PPM; FILM; CHIP; 0402")
      (fields (field (name "APPROVED") "CL"))
      (libsource (lib "Giga-tronics") (part "RK35-01400"))
    )
    (comp (ref "SW3")
      (value "[switches shown with IN=high]")
      (footprint "SOIC-16_Vishay")
      (description "QUAD SPST ANALOG SW;200NS;45 OHM;SO-16")
      (fields
        (field (name "G_PN") "ULD0-00613")
        (field (name "CLASSNAME") "SWA")
        (field (name "APPROVED") "NM")
      )
      (libsource (lib "Giga-tronics") (part "ULD0-00613_1"))
    )
    (comp (ref "SW4")
      (value "[switches shown with IN=high]")
      (footprint "SOIC-16_Vishay")
      (description "QUAD SPST ANALOG SW;200NS;45 OHM;SO-16")
      (fields
        (field (name "G_PN") "ULD0-00613")
        (field (name "CLASSNAME") "SWB")
        (field (name "APPROVED") "NM")
      )
      (libsource (lib "Giga-tronics") (part "ULD0-00613_1"))
    )
    (comp (ref "SW5")
      (value "[switches shown with IN=high]")
      (footprint "SOIC-16_Vishay")
      (description "QUAD SPST ANALOG SW;200NS;45 OHM;SO-16")
      (fields
        (field (name "G_PN") "ULD0-00613")
        (field (name "CLASSNAME") "SWC")
        (field (name "APPROVED") "NM")
      )
      (libsource (lib "Giga-tronics") (part "ULD0-00613_1"))
    )
    (comp (ref "SW6")
      (value "[switches shown with IN=high]")
      (footprint "SOIC-16_Vishay")
      (description "QUAD SPST ANALOG SW;200NS;45 OHM;SO-16")
      (fields
        (field (name "G_PN") "ULD0-00613")
        (field (name "CLASSNAME") "SWE")
        (field (name "APPROVED") "NM")
      )
      (libsource (lib "Giga-tronics") (part "ULD0-00613_1"))
    )
    (comp (ref "SW7")
      (value "[switches shown with IN=high]")
      (footprint "SOIC-16_Vishay")
      (description "QUAD SPST ANALOG SW;200NS;45 OHM;SO-16")
      (fields
        (field (name "G_PN") "ULD0-00613")
        (field (name "CLASSNAME") "SWF")
        (field (name "APPROVED") "NM")
      )
      (libsource (lib "Giga-tronics") (part "ULD0-00613_1"))
    )
    (comp (ref "SW8")
      (value "[switches shown with IN=high]")
      (footprint "SOIC-16_Vishay")
      (description "QUAD SPST ANALOG SW;200NS;45 OHM;SO-16")
      (fields
        (field (name "G_PN") "ULD0-00613")
        (field (name "CLASSNAME") "SWG")
        (field (name "APPROVED") "NM")
      )
      (libsource (lib "Giga-tronics") (part "ULD0-00613_1"))
    )
    (comp (ref "SW9")
      (value "[switches shown with IN=high]")
      (footprint "SOIC-16_Vishay")
      (description "QUAD SPST ANALOG SW;200NS;45 OHM;SO-16")
      (fields
        (field (name "G_PN") "ULD0-00613")
        (field (name "CLASSNAME") "SWH")
        (field (name "APPROVED") "NM")
      )
      (libsource (lib "Giga-tronics") (part "ULD0-00613_1"))
    )
    (comp (ref "SW10")
      (value "[switches shown with IN=high]")
      (footprint "SOIC-16_Vishay")
      (description "QUAD SPST ANALOG SW;200NS;45 OHM;SO-16")
      (fields
        (field (name "G_PN") "ULD0-00613")
        (field (name "CLASSNAME") "SWM")
        (field (name "APPROVED") "NM")
      )
      (libsource (lib "Giga-tronics") (part "ULD0-00613_1"))
    )
    (comp (ref "SW11")
      (value "[switches shown with IN=high]")
      (footprint "SOIC-16_Vishay")
      (description "QUAD SPST ANALOG SW;200NS;45 OHM;SO-16")
      (fields
        (field (name "G_PN") "ULD0-00613")
        (field (name "CLASSNAME") "SWL")
        (field (name "APPROVED") "NM")
      )
      (libsource (lib "Giga-tronics") (part "ULD0-00613_1"))
    )
    (comp (ref "SW12")
      (value "[switches shown with IN=high]")
      (footprint "SOIC-16_Vishay")
      (description "QUAD SPST ANALOG SW;200NS;45 OHM;SO-16")
      (fields
        (field (name "G_PN") "ULD0-00613")
        (field (name "CLASSNAME") "SWJ")
        (field (name "APPROVED") "NM")
      )
      (libsource (lib "Giga-tronics") (part "ULD0-00613_1"))
    )
    (comp (ref "SW13")
      (value "[switches shown with IN=high]")
      (footprint "SOIC-16_Vishay")
      (description "QUAD SPST ANALOG SW;200NS;45 OHM;SO-16")
      (fields
        (field (name "G_PN") "ULD0-00613")
        (field (name "CLASSNAME") "SWI")
        (field (name "APPROVED") "NM")
      )
      (libsource (lib "Giga-tronics") (part "ULD0-00613_1"))
    )
    (comp (ref "SW14")
      (value "[switches shown with IN=high]")
      (footprint "SOIC-16_Vishay")
      (description "QUAD SPST ANALOG SW;200NS;45 OHM;SO-16")
      (fields
        (field (name "G_PN") "ULD0-00613")
        (field (name "CLASSNAME") "SWK")
        (field (name "APPROVED") "NM")
      )
      (libsource (lib "Giga-tronics") (part "ULD0-00613_1"))
    )
    (comp (ref "SW22")
      (value "[switches shown with IN=high]")
      (footprint "SOIC-16_Vishay")
      (description "QUAD SPST ANALOG SW;200NS;45 OHM;SO-16")
      (fields
        (field (name "G_PN") "ULD0-00613")
        (field (name "CLASSNAME") "SWN")
        (field (name "APPROVED") "NM")
      )
      (libsource (lib "Giga-tronics") (part "ULD0-00613_1"))
    )
    (comp (ref "SW24")
      (value "[switches shown with IN=high]")
      (footprint "SOIC-16_Vishay")
      (description "QUAD SPST ANALOG SW;200NS;45 OHM;SO-16")
      (fields
        (field (name "G_PN") "ULD0-00613")
        (field (name "CLASSNAME") "SWD")
        (field (name "APPROVED") "NM")
      )
      (libsource (lib "Giga-tronics") (part "ULD0-00613_1"))
    )
    (comp (ref "SW301-1")
      (value "A1-A1: SW301-1")
      (footprint "JIB0-11254")
      (description "SOCKET;SINGLE;.018-.040 ID X .254;OPEN;GLD")
      (fields (field (name "APPROVED") "NM"))
      (libsource (lib "Giga-tronics") (part "JIB0-11254"))
    )
    (comp (ref "SW301-2")
      (value "A1-A1: SW301-2")
      (footprint "JIB0-11254")
      (description "SOCKET;SINGLE;.018-.040 ID X .254;OPEN;GLD")
      (fields (field (name "APPROVED") "NM"))
      (libsource (lib "Giga-tronics") (part "JIB0-11254"))
    )
    (comp (ref "SW301-3")
      (value "A1-A1: SW301-3")
      (footprint "JIB0-11254")
      (description "SOCKET;SINGLE;.018-.040 ID X .254;OPEN;GLD")
      (fields (field (name "APPROVED") "NM"))
      (libsource (lib "Giga-tronics") (part "JIB0-11254"))
    )
    (comp (ref "SW301-4")
      (value "A1-A1: SW301-4")
      (footprint "JIB0-11254")
      (description "SOCKET;SINGLE;.018-.040 ID X .254;OPEN;GLD")
      (fields (field (name "APPROVED") "NM"))
      (libsource (lib "Giga-tronics") (part "JIB0-11254"))
    )
    (comp (ref "SW301-5")
      (value "A1-A1: SW301-5")
      (footprint "JIB0-11254")
      (description "SOCKET;SINGLE;.018-.040 ID X .254;OPEN;GLD")
      (fields (field (name "APPROVED") "NM"))
      (libsource (lib "Giga-tronics") (part "JIB0-11254"))
    )
    (comp (ref "SW301-6")
      (value "A1-A1: SW301-6")
      (footprint "JIB0-11254")
      (description "SOCKET;SINGLE;.018-.040 ID X .254;OPEN;GLD")
      (fields (field (name "APPROVED") "NM"))
      (libsource (lib "Giga-tronics") (part "JIB0-11254"))
    )
    (comp (ref "SW302-1")
      (value "A1-A1: SW302-1")
      (footprint "JIB0-11254")
      (description "SOCKET;SINGLE;.018-.040 ID X .254;OPEN;GLD")
      (fields (field (name "APPROVED") "NM"))
      (libsource (lib "Giga-tronics") (part "JIB0-11254"))
    )
    (comp (ref "SW302-2")
      (value "A1-A1: SW302-2")
      (footprint "JIB0-11254")
      (description "SOCKET;SINGLE;.018-.040 ID X .254;OPEN;GLD")
      (fields (field (name "APPROVED") "NM"))
      (libsource (lib "Giga-tronics") (part "JIB0-11254"))
    )
    (comp (ref "SW302-3")
      (value "A1-A1: SW302-3")
      (footprint "JIB0-11254")
      (description "SOCKET;SINGLE;.018-.040 ID X .254;OPEN;GLD")
      (fields (field (name "APPROVED") "NM"))
      (libsource (lib "Giga-tronics") (part "JIB0-11254"))
    )
    (comp (ref "SW302-4")
      (value "A1-A1: SW302-4")
      (footprint "JIB0-11254")
      (description "SOCKET;SINGLE;.018-.040 ID X .254;OPEN;GLD")
      (fields (field (name "APPROVED") "NM"))
      (libsource (lib "Giga-tronics") (part "JIB0-11254"))
    )
    (comp (ref "SW302-5")
      (value "A1-A1: SW302-5")
      (footprint "JIB0-11254")
      (description "SOCKET;SINGLE;.018-.040 ID X .254;OPEN;GLD")
      (fields (field (name "APPROVED") "NM"))
      (libsource (lib "Giga-tronics") (part "JIB0-11254"))
    )
    (comp (ref "SW302-6")
      (value "A1-A1: SW302-6")
      (footprint "JIB0-11254")
      (description "SOCKET;SINGLE;.018-.040 ID X .254;OPEN;GLD")
      (fields (field (name "APPROVED") "NM"))
      (libsource (lib "Giga-tronics") (part "JIB0-11254"))
    )
    (comp (ref "SW303-1")
      (value "A1-A1: SW303-1")
      (footprint "JIB0-11254")
      (description "SOCKET;SINGLE;.018-.040 ID X .254;OPEN;GLD")
      (fields (field (name "APPROVED") "NM"))
      (libsource (lib "Giga-tronics") (part "JIB0-11254"))
    )
    (comp (ref "SW303-2")
      (value "A1-A1: SW303-2")
      (footprint "JIB0-11254")
      (description "SOCKET;SINGLE;.018-.040 ID X .254;OPEN;GLD")
      (fields (field (name "APPROVED") "NM"))
      (libsource (lib "Giga-tronics") (part "JIB0-11254"))
    )
    (comp (ref "SW303-3")
      (value "A1-A1: SW303-3")
      (footprint "JIB0-11254")
      (description "SOCKET;SINGLE;.018-.040 ID X .254;OPEN;GLD")
      (fields (field (name "APPROVED") "NM"))
      (libsource (lib "Giga-tronics") (part "JIB0-11254"))
    )
    (comp (ref "SW303-4")
      (value "A1-A1: SW303-4")
      (footprint "JIB0-11254")
      (description "SOCKET;SINGLE;.018-.040 ID X .254;OPEN;GLD")
      (fields (field (name "APPROVED") "NM"))
      (libsource (lib "Giga-tronics") (part "JIB0-11254"))
    )
    (comp (ref "SW303-5")
      (value "A1-A1: SW303-5")
      (footprint "JIB0-11254")
      (description "SOCKET;SINGLE;.018-.040 ID X .254;OPEN;GLD")
      (fields (field (name "APPROVED") "NM"))
      (libsource (lib "Giga-tronics") (part "JIB0-11254"))
    )
    (comp (ref "SW303-6")
      (value "A1-A1: SW303-6")
      (footprint "JIB0-11254")
      (description "SOCKET;SINGLE;.018-.040 ID X .254;OPEN;GLD")
      (fields (field (name "APPROVED") "NM"))
      (libsource (lib "Giga-tronics") (part "JIB0-11254"))
    )
    (comp (ref "SW304-1")
      (value "A1-A1: SW304-1")
      (footprint "JIB0-11254")
      (description "SOCKET;SINGLE;.018-.040 ID X .254;OPEN;GLD")
      (fields (field (name "APPROVED") "NM"))
      (libsource (lib "Giga-tronics") (part "JIB0-11254"))
    )
    (comp (ref "SW304-2")
      (value "A1-A1: SW304-2")
      (footprint "JIB0-11254")
      (description "SOCKET;SINGLE;.018-.040 ID X .254;OPEN;GLD")
      (fields (field (name "APPROVED") "NM"))
      (libsource (lib "Giga-tronics") (part "JIB0-11254"))
    )
    (comp (ref "SW304-3")
      (value "A1-A1: SW304-3")
      (footprint "JIB0-11254")
      (description "SOCKET;SINGLE;.018-.040 ID X .254;OPEN;GLD")
      (fields (field (name "APPROVED") "NM"))
      (libsource (lib "Giga-tronics") (part "JIB0-11254"))
    )
    (comp (ref "SW304-4")
      (value "A1-A1: SW304-4")
      (footprint "JIB0-11254")
      (description "SOCKET;SINGLE;.018-.040 ID X .254;OPEN;GLD")
      (fields (field (name "APPROVED") "NM"))
      (libsource (lib "Giga-tronics") (part "JIB0-11254"))
    )
    (comp (ref "SW304-5")
      (value "A1-A1: SW304-5")
      (footprint "JIB0-11254")
      (description "SOCKET;SINGLE;.018-.040 ID X .254;OPEN;GLD")
      (fields (field (name "APPROVED") "NM"))
      (libsource (lib "Giga-tronics") (part "JIB0-11254"))
    )
    (comp (ref "SW304-6")
      (value "A1-A1: SW304-6")
      (footprint "JIB0-11254-TRIM")
      (description "SOCKET;SINGLE;.018-.040 ID X .254;OPEN;GLD")
      (fields (field (name "G_PN") "JIB0-11254"))
      (libsource (lib "Giga-tronics") (part "JIB0-11254_Trim"))
    )
    (comp (ref "T18")
      (value "A1-A1: T18")
      (footprint "JIB0-11254")
      (description "SOCKET;SINGLE;.018-.040 ID X .254;OPEN;GLD")
      (fields (field (name "APPROVED") "NM"))
      (libsource (lib "Giga-tronics") (part "JIB0-11254"))
    )
    (comp (ref "T19")
      (value "A1-A1: T19")
      (footprint "JIB0-11254")
      (description "SOCKET;SINGLE;.018-.040 ID X .254;OPEN;GLD")
      (fields (field (name "APPROVED") "NM"))
      (libsource (lib "Giga-tronics") (part "JIB0-11254"))
    )
    (comp (ref "T20")
      (value "A1-A1: T20")
      (footprint "JIB0-11254")
      (description "SOCKET;SINGLE;.018-.040 ID X .254;OPEN;GLD")
      (fields (field (name "APPROVED") "NM"))
      (libsource (lib "Giga-tronics") (part "JIB0-11254"))
    )
    (comp (ref "T21")
      (value "A1-A1: T21")
      (footprint "JIB0-11254")
      (description "SOCKET;SINGLE;.018-.040 ID X .254;OPEN;GLD")
      (fields (field (name "APPROVED") "NM"))
      (libsource (lib "Giga-tronics") (part "JIB0-11254"))
    )
    (comp (ref "T22")
      (value "A1-A1: T22")
      (footprint "JIB0-11254")
      (description "SOCKET;SINGLE;.018-.040 ID X .254;OPEN;GLD")
      (fields (field (name "APPROVED") "NM"))
      (libsource (lib "Giga-tronics") (part "JIB0-11254"))
    )
    (comp (ref "T23")
      (value "A1-A1: T23")
      (footprint "JIB0-11254")
      (description "SOCKET;SINGLE;.018-.040 ID X .254;OPEN;GLD")
      (fields (field (name "APPROVED") "NM"))
      (libsource (lib "Giga-tronics") (part "JIB0-11254"))
    )
    (comp (ref "T24")
      (value "A1-A1: T24")
      (footprint "JIB0-11254")
      (description "SOCKET;SINGLE;.018-.040 ID X .254;OPEN;GLD")
      (fields (field (name "APPROVED") "NM"))
      (libsource (lib "Giga-tronics") (part "JIB0-11254"))
    )
    (comp (ref "T25")
      (value "A1-A1: T25")
      (footprint "JIB0-11254")
      (description "SOCKET;SINGLE;.018-.040 ID X .254;OPEN;GLD")
      (fields (field (name "APPROVED") "NM"))
      (libsource (lib "Giga-tronics") (part "JIB0-11254"))
    )
    (comp (ref "T26")
      (value "A1-A1: T26")
      (footprint "JIB0-11254")
      (description "SOCKET;SINGLE;.018-.040 ID X .254;OPEN;GLD")
      (fields (field (name "APPROVED") "NM"))
      (libsource (lib "Giga-tronics") (part "JIB0-11254"))
    )
    (comp (ref "T27")
      (value "A1-A1: T27")
      (footprint "JIB0-11254")
      (description "SOCKET;SINGLE;.018-.040 ID X .254;OPEN;GLD")
      (fields (field (name "APPROVED") "NM"))
      (libsource (lib "Giga-tronics") (part "JIB0-11254"))
    )
    (comp (ref "T28")
      (value "A1-A1: T28")
      (footprint "JIB0-11254")
      (description "SOCKET;SINGLE;.018-.040 ID X .254;OPEN;GLD")
      (fields (field (name "APPROVED") "NM"))
      (libsource (lib "Giga-tronics") (part "JIB0-11254"))
    )
    (comp (ref "T29")
      (value "A1-A1: T29")
      (footprint "JIB0-11254")
      (description "SOCKET;SINGLE;.018-.040 ID X .254;OPEN;GLD")
      (fields (field (name "APPROVED") "NM"))
      (libsource (lib "Giga-tronics") (part "JIB0-11254"))
    )
    (comp (ref "T30")
      (value "A1-A1: T30")
      (footprint "JIB0-11254")
      (description "SOCKET;SINGLE;.018-.040 ID X .254;OPEN;GLD")
      (fields (field (name "APPROVED") "NM"))
      (libsource (lib "Giga-tronics") (part "JIB0-11254"))
    )
    (comp (ref "T31")
      (value "A1-A1: T31")
      (footprint "JIB0-11254")
      (description "SOCKET;SINGLE;.018-.040 ID X .254;OPEN;GLD")
      (fields (field (name "APPROVED") "NM"))
      (libsource (lib "Giga-tronics") (part "JIB0-11254"))
    )
    (comp (ref "T32")
      (value "A1-A1: T32")
      (footprint "JIB0-11254")
      (description "SOCKET;SINGLE;.018-.040 ID X .254;OPEN;GLD")
      (fields (field (name "APPROVED") "NM"))
      (libsource (lib "Giga-tronics") (part "JIB0-11254"))
    )
    (comp (ref "T33")
      (value "A1-A1: T33")
      (footprint "JIB0-11254")
      (description "SOCKET;SINGLE;.018-.040 ID X .254;OPEN;GLD")
      (fields (field (name "APPROVED") "NM"))
      (libsource (lib "Giga-tronics") (part "JIB0-11254"))
    )
    (comp (ref "T41")
      (value "A1-A1: T41")
      (footprint "JIB0-11254")
      (description "SOCKET;SINGLE;.018-.040 ID X .254;OPEN;GLD")
      (fields (field (name "APPROVED") "NM"))
      (libsource (lib "Giga-tronics") (part "JIB0-11254"))
    )
    (comp (ref "T42")
      (value "A1-A1: T42")
      (footprint "JIB0-11254")
      (description "SOCKET;SINGLE;.018-.040 ID X .254;OPEN;GLD")
      (fields (field (name "APPROVED") "NM"))
      (libsource (lib "Giga-tronics") (part "JIB0-11254"))
    )
    (comp (ref "T45")
      (value "A1-A1: T45")
      (footprint "JIB0-11254")
      (description "SOCKET;SINGLE;.018-.040 ID X .254;OPEN;GLD")
      (fields (field (name "APPROVED") "NM"))
      (libsource (lib "Giga-tronics") (part "JIB0-11254"))
    )
    (comp (ref "T46")
      (value "A1-A1: T46")
      (footprint "JIB0-11254")
      (description "SOCKET;SINGLE;.018-.040 ID X .254;OPEN;GLD")
      (fields (field (name "APPROVED") "NM"))
      (libsource (lib "Giga-tronics") (part "JIB0-11254"))
    )
    (comp (ref "T62")
      (value "A1-A1: T62")
      (footprint "JIB0-11254")
      (description "SOCKET;SINGLE;.018-.040 ID X .254;OPEN;GLD")
      (fields (field (name "APPROVED") "NM"))
      (libsource (lib "Giga-tronics") (part "JIB0-11254"))
    )
    (comp (ref "T63")
      (value "A1-A1: T63")
      (footprint "JIB0-11254")
      (description "SOCKET;SINGLE;.018-.040 ID X .254;OPEN;GLD")
      (fields (field (name "APPROVED") "NM"))
      (libsource (lib "Giga-tronics") (part "JIB0-11254"))
    )
    (comp (ref "T73")
      (value "A1-A1: T73")
      (footprint "JIB0-11254")
      (description "SOCKET;SINGLE;.018-.040 ID X .254;OPEN;GLD")
      (fields (field (name "APPROVED") "NM"))
      (libsource (lib "Giga-tronics") (part "JIB0-11254"))
    )
    (comp (ref "T74")
      (value "A1-A1: T74")
      (footprint "JIB0-11254")
      (description "SOCKET;SINGLE;.018-.040 ID X .254;OPEN;GLD")
      (fields (field (name "APPROVED") "NM"))
      (libsource (lib "Giga-tronics") (part "JIB0-11254"))
    )
    (comp (ref "T75")
      (value "A1-A1: T75")
      (footprint "JIB0-11254")
      (description "SOCKET;SINGLE;.018-.040 ID X .254;OPEN;GLD")
      (fields (field (name "APPROVED") "NM"))
      (libsource (lib "Giga-tronics") (part "JIB0-11254"))
    )
    (comp (ref "T76")
      (value "A1-A1: T76")
      (footprint "JIB0-11254")
      (description "SOCKET;SINGLE;.018-.040 ID X .254;OPEN;GLD")
      (fields (field (name "APPROVED") "NM"))
      (libsource (lib "Giga-tronics") (part "JIB0-11254"))
    )
    (comp (ref "T80")
      (value "A1-A1: T80")
      (footprint "JIB0-11254")
      (description "SOCKET;SINGLE;.018-.040 ID X .254;OPEN;GLD")
      (fields (field (name "APPROVED") "NM"))
      (libsource (lib "Giga-tronics") (part "JIB0-11254"))
    )
    (comp (ref "T81")
      (value "A1-A1: T81")
      (footprint "JIB0-11254")
      (description "SOCKET;SINGLE;.018-.040 ID X .254;OPEN;GLD")
      (fields (field (name "APPROVED") "NM"))
      (libsource (lib "Giga-tronics") (part "JIB0-11254"))
    )
    (comp (ref "T82")
      (value "A1-A1: T82")
      (footprint "JIB0-11254")
      (description "SOCKET;SINGLE;.018-.040 ID X .254;OPEN;GLD")
      (fields (field (name "APPROVED") "NM"))
      (libsource (lib "Giga-tronics") (part "JIB0-11254"))
    )
    (comp (ref "T83")
      (value "A1-A1: T83")
      (footprint "JIB0-11254")
      (description "SOCKET;SINGLE;.018-.040 ID X .254;OPEN;GLD")
      (fields (field (name "APPROVED") "NM"))
      (libsource (lib "Giga-tronics") (part "JIB0-11254"))
    )
    (comp (ref "TP21")
      (value ".")
      (footprint "TP-060")
      (fields (field (name "NOLOAD") "N/L") (field (name "APPROVED") "NM"))
      (libsource (lib "Giga-tronics") (part "TP-060"))
    )
    (comp (ref "TP22")
      (value ".")
      (footprint "TP-060")
      (fields (field (name "NOLOAD") "N/L") (field (name "APPROVED") "NM"))
      (libsource (lib "Giga-tronics") (part "TP-060"))
    )
    (comp (ref "TP23")
      (value ".")
      (footprint "TP-060")
      (fields (field (name "NOLOAD") "N/L") (field (name "APPROVED") "NM"))
      (libsource (lib "Giga-tronics") (part "TP-060"))
    )
    (comp (ref "TP24")
      (value ".")
      (footprint "TP-060")
      (fields (field (name "NOLOAD") "N/L") (field (name "APPROVED") "NM"))
      (libsource (lib "Giga-tronics") (part "TP-060"))
    )
    (comp (ref "TP25")
      (value ".")
      (footprint "TP-060")
      (fields (field (name "NOLOAD") "N/L") (field (name "APPROVED") "NM"))
      (libsource (lib "Giga-tronics") (part "TP-060"))
    )
    (comp (ref "TP26")
      (value ".")
      (footprint "TP-060")
      (fields (field (name "NOLOAD") "N/L") (field (name "APPROVED") "NM"))
      (libsource (lib "Giga-tronics") (part "TP-060"))
    )
    (comp (ref "TP27")
      (value ".")
      (footprint "TP-060")
      (fields (field (name "NOLOAD") "N/L") (field (name "APPROVED") "NM"))
      (libsource (lib "Giga-tronics") (part "TP-060"))
    )
    (comp (ref "TP28")
      (value ".")
      (footprint "TP-060")
      (fields (field (name "NOLOAD") "N/L") (field (name "APPROVED") "NM"))
      (libsource (lib "Giga-tronics") (part "TP-060"))
    )
    (comp (ref "TP29")
      (value ".")
      (footprint "TP-060")
      (fields (field (name "NOLOAD") "N/L") (field (name "APPROVED") "NM"))
      (libsource (lib "Giga-tronics") (part "TP-060"))
    )
    (comp (ref "TP30")
      (value ".")
      (footprint "TP-060")
      (fields (field (name "NOLOAD") "N/L") (field (name "APPROVED") "NM"))
      (libsource (lib "Giga-tronics") (part "TP-060"))
    )
    (comp (ref "TP31")
      (value ".")
      (footprint "TP-060")
      (fields (field (name "NOLOAD") "N/L") (field (name "APPROVED") "NM"))
      (libsource (lib "Giga-tronics") (part "TP-060"))
    )
    (comp (ref "TP32")
      (value ".")
      (footprint "TP-060")
      (fields (field (name "NOLOAD") "N/L") (field (name "APPROVED") "NM"))
      (libsource (lib "Giga-tronics") (part "TP-060"))
    )
    (comp (ref "TP33")
      (value ".")
      (footprint "TP-060")
      (fields (field (name "NOLOAD") "N/L") (field (name "APPROVED") "NM"))
      (libsource (lib "Giga-tronics") (part "TP-060"))
    )
    (comp (ref "TP34")
      (value ".")
      (footprint "TP-060")
      (fields (field (name "NOLOAD") "N/L") (field (name "APPROVED") "NM"))
      (libsource (lib "Giga-tronics") (part "TP-060"))
    )
    (comp (ref "TP35")
      (value ".")
      (footprint "TP-060")
      (fields (field (name "NOLOAD") "N/L") (field (name "APPROVED") "NM"))
      (libsource (lib "Giga-tronics") (part "TP-060"))
    )
    (comp (ref "TP36")
      (value ".")
      (footprint "TP-060")
      (fields (field (name "NOLOAD") "N/L") (field (name "APPROVED") "NM"))
      (libsource (lib "Giga-tronics") (part "TP-060"))
    )
    (comp (ref "TP37")
      (value ".")
      (footprint "TP-060")
      (fields (field (name "NOLOAD") "N/L") (field (name "APPROVED") "NM"))
      (libsource (lib "Giga-tronics") (part "TP-060"))
    )
    (comp (ref "TP38")
      (value ".")
      (footprint "TP-060")
      (fields (field (name "NOLOAD") "N/L") (field (name "APPROVED") "NM"))
      (libsource (lib "Giga-tronics") (part "TP-060"))
    )
    (comp (ref "TP39")
      (value ".")
      (footprint "TP-060")
      (fields (field (name "NOLOAD") "N/L") (field (name "APPROVED") "NM"))
      (libsource (lib "Giga-tronics") (part "TP-060"))
    )
    (comp (ref "TP40")
      (value ".")
      (footprint "TP-060")
      (fields (field (name "NOLOAD") "N/L") (field (name "APPROVED") "NM"))
      (libsource (lib "Giga-tronics") (part "TP-060"))
    )
    (comp (ref "TP41")
      (value ".")
      (footprint "TP-060")
      (fields (field (name "NOLOAD") "N/L") (field (name "APPROVED") "NM"))
      (libsource (lib "Giga-tronics") (part "TP-060"))
    )
    (comp (ref "TP42")
      (value ".")
      (footprint "TP-060")
      (fields (field (name "NOLOAD") "N/L") (field (name "APPROVED") "NM"))
      (libsource (lib "Giga-tronics") (part "TP-060"))
    )
    (comp (ref "TP43")
      (value ".")
      (footprint "TP-060")
      (fields (field (name "NOLOAD") "N/L") (field (name "APPROVED") "NM"))
      (libsource (lib "Giga-tronics") (part "TP-060"))
    )
    (comp (ref "TP44")
      (value ".")
      (footprint "TP-060")
      (fields (field (name "NOLOAD") "N/L") (field (name "APPROVED") "NM"))
      (libsource (lib "Giga-tronics") (part "TP-060"))
    )
    (comp (ref "TP45")
      (value ".")
      (footprint "TP-060")
      (fields (field (name "NOLOAD") "N/L") (field (name "APPROVED") "NM"))
      (libsource (lib "Giga-tronics") (part "TP-060"))
    )
    (comp (ref "TP46")
      (value ".")
      (footprint "TP-060")
      (fields (field (name "NOLOAD") "N/L") (field (name "APPROVED") "NM"))
      (libsource (lib "Giga-tronics") (part "TP-060"))
    )
    (comp (ref "TP47")
      (value ".")
      (footprint "TP-060")
      (fields (field (name "NOLOAD") "N/L") (field (name "APPROVED") "NM"))
      (libsource (lib "Giga-tronics") (part "TP-060"))
    )
    (comp (ref "TP48")
      (value ".")
      (footprint "TP-060")
      (fields (field (name "NOLOAD") "N/L") (field (name "APPROVED") "NM"))
      (libsource (lib "Giga-tronics") (part "TP-060"))
    )
  )
  (nets
    (net (code "1") (name "+5V_SW") (class "Default")
      (node (ref "C134") (pin "2") (pintype "passive"))
      (node (ref "C135") (pin "2") (pintype "passive"))
      (node (ref "C136") (pin "2") (pintype "passive"))
      (node (ref "C137") (pin "2") (pintype "passive"))
      (node (ref "C138") (pin "2") (pintype "passive"))
      (node (ref "C154") (pin "2") (pintype "passive"))
      (node (ref "C574") (pin "2") (pintype "passive"))
      (node (ref "C582") (pin "2") (pintype "passive"))
      (node (ref "C628") (pin "2") (pintype "passive"))
      (node (ref "C629") (pin "2") (pintype "passive"))
      (node (ref "C630") (pin "2") (pintype "passive"))
      (node (ref "C631") (pin "2") (pintype "passive"))
      (node (ref "C632") (pin "2") (pintype "passive"))
      (node (ref "C633") (pin "2") (pintype "passive"))
      (node (ref "C634") (pin "2") (pintype "passive"))
      (node (ref "C635") (pin "2") (pintype "passive"))
      (node (ref "C642") (pin "2") (pintype "passive"))
      (node (ref "C643") (pin "2") (pintype "passive"))
      (node (ref "C644") (pin "2") (pintype "passive"))
      (node (ref "C645") (pin "2") (pintype "passive"))
      (node (ref "C648") (pin "2") (pintype "passive"))
      (node (ref "C649") (pin "2") (pintype "passive"))
      (node (ref "C650") (pin "2") (pintype "passive"))
      (node (ref "C651") (pin "2") (pintype "passive"))
      (node (ref "C655") (pin "2") (pintype "passive"))
      (node (ref "C656") (pin "2") (pintype "passive"))
      (node (ref "C657") (pin "2") (pintype "passive"))
      (node (ref "C658") (pin "2") (pintype "passive"))
      (node (ref "C659") (pin "2") (pintype "passive"))
      (node (ref "C660") (pin "2") (pintype "passive"))
      (node (ref "C661") (pin "2") (pintype "passive"))
      (node (ref "C662") (pin "2") (pintype "passive"))
      (node (ref "C673") (pin "2") (pintype "passive"))
      (node (ref "C674") (pin "2") (pintype "passive"))
      (node (ref "C675") (pin "2") (pintype "passive"))
      (node (ref "C676") (pin "2") (pintype "passive"))
      (node (ref "C677") (pin "2") (pintype "passive"))
      (node (ref "C678") (pin "2") (pintype "passive"))
      (node (ref "C679") (pin "2") (pintype "passive"))
      (node (ref "C680") (pin "2") (pintype "passive"))
      (node (ref "C685") (pin "2") (pintype "passive"))
      (node (ref "C686") (pin "2") (pintype "passive"))
      (node (ref "C687") (pin "2") (pintype "passive"))
      (node (ref "C688") (pin "2") (pintype "passive"))
      (node (ref "C689") (pin "2") (pintype "passive"))
      (node (ref "C690") (pin "2") (pintype "passive"))
      (node (ref "C691") (pin "2") (pintype "passive"))
      (node (ref "C692") (pin "2") (pintype "passive"))
      (node (ref "C698") (pin "2") (pintype "passive"))
      (node (ref "C699") (pin "2") (pintype "passive"))
      (node (ref "C701") (pin "2") (pintype "passive"))
      (node (ref "C702") (pin "2") (pintype "passive"))
      (node (ref "C705") (pin "2") (pintype "passive"))
      (node (ref "C706") (pin "2") (pintype "passive"))
      (node (ref "C708") (pin "2") (pintype "passive"))
      (node (ref "C709") (pin "2") (pintype "passive"))
      (node (ref "FT35") (pin "1") (pinfunction "1_1") (pintype "passive"))
      (node (ref "R117") (pin "2") (pintype "passive"))
      (node (ref "R119") (pin "2") (pintype "passive"))
      (node (ref "R120") (pin "2") (pintype "passive"))
      (node (ref "R121") (pin "2") (pintype "passive"))
      (node (ref "R122") (pin "2") (pintype "passive"))
      (node (ref "R123") (pin "2") (pintype "passive"))
      (node (ref "R124") (pin "2") (pintype "passive"))
      (node (ref "R125") (pin "2") (pintype "passive"))
      (node (ref "R136") (pin "2") (pintype "passive"))
      (node (ref "R137") (pin "2") (pintype "passive"))
      (node (ref "R138") (pin "2") (pintype "passive"))
      (node (ref "R139") (pin "2") (pintype "passive"))
      (node (ref "R140") (pin "2") (pintype "passive"))
      (node (ref "R141") (pin "2") (pintype "passive"))
      (node (ref "R142") (pin "2") (pintype "passive"))
      (node (ref "R143") (pin "2") (pintype "passive"))
      (node (ref "R152") (pin "2") (pintype "passive"))
      (node (ref "R153") (pin "2") (pintype "passive"))
      (node (ref "R154") (pin "2") (pintype "passive"))
      (node (ref "R155") (pin "2") (pintype "passive"))
      (node (ref "R156") (pin "2") (pintype "passive"))
      (node (ref "R157") (pin "2") (pintype "passive"))
      (node (ref "R158") (pin "2") (pintype "passive"))
      (node (ref "R159") (pin "2") (pintype "passive"))
      (node (ref "R247") (pin "2") (pintype "passive"))
      (node (ref "R248") (pin "2") (pintype "passive"))
      (node (ref "R365") (pin "2") (pintype "passive"))
      (node (ref "R366") (pin "2") (pintype "passive"))
      (node (ref "SW10") (pin "12") (pinfunction "VL_12") (pintype "passive"))
      (node (ref "SW10") (pin "13") (pinfunction "V+_13") (pintype "passive"))
      (node (ref "SW11") (pin "12") (pinfunction "VL_12") (pintype "passive"))
      (node (ref "SW11") (pin "13") (pinfunction "V+_13") (pintype "passive"))
      (node (ref "SW12") (pin "12") (pinfunction "VL_12") (pintype "passive"))
      (node (ref "SW12") (pin "13") (pinfunction "V+_13") (pintype "passive"))
      (node (ref "SW13") (pin "12") (pinfunction "VL_12") (pintype "passive"))
      (node (ref "SW13") (pin "13") (pinfunction "V+_13") (pintype "passive"))
      (node (ref "SW14") (pin "12") (pinfunction "VL_12") (pintype "passive"))
      (node (ref "SW14") (pin "13") (pinfunction "V+_13") (pintype "passive"))
      (node (ref "SW22") (pin "12") (pinfunction "VL_12") (pintype "passive"))
      (node (ref "SW22") (pin "13") (pinfunction "V+_13") (pintype "passive"))
      (node (ref "SW24") (pin "12") (pinfunction "VL_12") (pintype "passive"))
      (node (ref "SW24") (pin "13") (pinfunction "V+_13") (pintype "passive"))
      (node (ref "SW3") (pin "12") (pinfunction "VL_12") (pintype "passive"))
      (node (ref "SW3") (pin "13") (pinfunction "V+_13") (pintype "passive"))
      (node (ref "SW4") (pin "12") (pinfunction "VL_12") (pintype "passive"))
      (node (ref "SW4") (pin "13") (pinfunction "V+_13") (pintype "passive"))
      (node (ref "SW5") (pin "12") (pinfunction "VL_12") (pintype "passive"))
      (node (ref "SW5") (pin "13") (pinfunction "V+_13") (pintype "passive"))
      (node (ref "SW6") (pin "12") (pinfunction "VL_12") (pintype "passive"))
      (node (ref "SW6") (pin "13") (pinfunction "V+_13") (pintype "passive"))
      (node (ref "SW7") (pin "12") (pinfunction "VL_12") (pintype "passive"))
      (node (ref "SW7") (pin "13") (pinfunction "V+_13") (pintype "passive"))
      (node (ref "SW8") (pin "12") (pinfunction "VL_12") (pintype "passive"))
      (node (ref "SW8") (pin "13") (pinfunction "V+_13") (pintype "passive"))
      (node (ref "SW9") (pin "12") (pinfunction "VL_12") (pintype "passive"))
      (node (ref "SW9") (pin "13") (pinfunction "V+_13") (pintype "passive"))
    )
    (net (code "2") (name "-5V_SW") (class "Default")
      (node (ref "C130") (pin "2") (pintype "passive"))
      (node (ref "C131") (pin "2") (pintype "passive"))
      (node (ref "C132") (pin "2") (pintype "passive"))
      (node (ref "C133") (pin "2") (pintype "passive"))
      (node (ref "C583") (pin "2") (pintype "passive"))
      (node (ref "C584") (pin "2") (pintype "passive"))
      (node (ref "C585") (pin "2") (pintype "passive"))
      (node (ref "C627") (pin "2") (pintype "passive"))
      (node (ref "C636") (pin "2") (pintype "passive"))
      (node (ref "C637") (pin "2") (pintype "passive"))
      (node (ref "C638") (pin "2") (pintype "passive"))
      (node (ref "C639") (pin "2") (pintype "passive"))
      (node (ref "C640") (pin "2") (pintype "passive"))
      (node (ref "C641") (pin "2") (pintype "passive"))
      (node (ref "C646") (pin "2") (pintype "passive"))
      (node (ref "C647") (pin "2") (pintype "passive"))
      (node (ref "C652") (pin "2") (pintype "passive"))
      (node (ref "C653") (pin "2") (pintype "passive"))
      (node (ref "FT8") (pin "1") (pinfunction "1_1") (pintype "passive"))
      (node (ref "R109") (pin "2") (pintype "passive"))
      (node (ref "R110") (pin "2") (pintype "passive"))
      (node (ref "R111") (pin "2") (pintype "passive"))
      (node (ref "R116") (pin "2") (pintype "passive"))
      (node (ref "R126") (pin "2") (pintype "passive"))
      (node (ref "R127") (pin "2") (pintype "passive"))
      (node (ref "R128") (pin "2") (pintype "passive"))
      (node (ref "R129") (pin "2") (pintype "passive"))
      (node (ref "R134") (pin "2") (pintype "passive"))
      (node (ref "R135") (pin "2") (pintype "passive"))
      (node (ref "R146") (pin "2") (pintype "passive"))
      (node (ref "R147") (pin "2") (pintype "passive"))
      (node (ref "SW3") (pin "4") (pinfunction "VL_4") (pintype "passive"))
      (node (ref "SW4") (pin "4") (pinfunction "VL_4") (pintype "passive"))
      (node (ref "SW5") (pin "4") (pinfunction "VL_4") (pintype "passive"))
      (node (ref "SW6") (pin "4") (pinfunction "VL_4") (pintype "passive"))
      (node (ref "SW7") (pin "4") (pinfunction "VL_4") (pintype "passive"))
      (node (ref "SW8") (pin "4") (pinfunction "VL_4") (pintype "passive"))
    )
    (net (code "3") (name "-12V_SW") (class "Default")
      (node (ref "C663") (pin "2") (pintype "passive"))
      (node (ref "C664") (pin "2") (pintype "passive"))
      (node (ref "C665") (pin "1") (pintype "passive"))
      (node (ref "C666") (pin "1") (pintype "passive"))
      (node (ref "C667") (pin "1") (pintype "passive"))
      (node (ref "C668") (pin "1") (pintype "passive"))
      (node (ref "C669") (pin "1") (pintype "passive"))
      (node (ref "C670") (pin "1") (pintype "passive"))
      (node (ref "C671") (pin "1") (pintype "passive"))
      (node (ref "C672") (pin "1") (pintype "passive"))
      (node (ref "C681") (pin "1") (pintype "passive"))
      (node (ref "C682") (pin "1") (pintype "passive"))
      (node (ref "C683") (pin "1") (pintype "passive"))
      (node (ref "C684") (pin "1") (pintype "passive"))
      (node (ref "C693") (pin "2") (pintype "passive"))
      (node (ref "C694") (pin "2") (pintype "passive"))
      (node (ref "C695") (pin "2") (pintype "passive"))
      (node (ref "C696") (pin "2") (pintype "passive"))
      (node (ref "C697") (pin "1") (pintype "passive"))
      (node (ref "C700") (pin "1") (pintype "passive"))
      (node (ref "C703") (pin "2") (pintype "passive"))
      (node (ref "C704") (pin "2") (pintype "passive"))
      (node (ref "C707") (pin "2") (pintype "passive"))
      (node (ref "C710") (pin "2") (pintype "passive"))
      (node (ref "FT4") (pin "1") (pinfunction "1_1") (pintype "passive"))
      (node (ref "R130") (pin "2") (pintype "passive"))
      (node (ref "R132") (pin "2") (pintype "passive"))
      (node (ref "R144") (pin "2") (pintype "passive"))
      (node (ref "R145") (pin "2") (pintype "passive"))
      (node (ref "R148") (pin "2") (pintype "passive"))
      (node (ref "R149") (pin "2") (pintype "passive"))
      (node (ref "R150") (pin "2") (pintype "passive"))
      (node (ref "R151") (pin "2") (pintype "passive"))
      (node (ref "R160") (pin "2") (pintype "passive"))
      (node (ref "R161") (pin "2") (pintype "passive"))
      (node (ref "R162") (pin "2") (pintype "passive"))
      (node (ref "R163") (pin "2") (pintype "passive"))
      (node (ref "R246") (pin "2") (pintype "passive"))
      (node (ref "R249") (pin "2") (pintype "passive"))
      (node (ref "R349") (pin "2") (pintype "passive"))
      (node (ref "R367") (pin "2") (pintype "passive"))
      (node (ref "SW10") (pin "4") (pinfunction "VL_4") (pintype "passive"))
      (node (ref "SW11") (pin "4") (pinfunction "VL_4") (pintype "passive"))
      (node (ref "SW12") (pin "4") (pinfunction "VL_4") (pintype "passive"))
      (node (ref "SW13") (pin "4") (pinfunction "VL_4") (pintype "passive"))
      (node (ref "SW14") (pin "4") (pinfunction "VL_4") (pintype "passive"))
      (node (ref "SW22") (pin "4") (pinfunction "VL_4") (pintype "passive"))
      (node (ref "SW24") (pin "4") (pinfunction "VL_4") (pintype "passive"))
      (node (ref "SW9") (pin "4") (pinfunction "VL_4") (pintype "passive"))
    )
    (net (code "4") (name "/2-8.3") (class "Default")
      (node (ref "SW3") (pin "1") (pinfunction "IN1_1") (pintype "passive"))
      (node (ref "SW3") (pin "16") (pinfunction "S1_16") (pintype "passive"))
    )
    (net (code "5") (name "/8.3-10.2") (class "Default")
      (node (ref "SW3") (pin "8") (pinfunction "IN4_8") (pintype "passive"))
      (node (ref "SW3") (pin "9") (pinfunction "IN3_9") (pintype "passive"))
    )
    (net (code "6") (name "/8.3_GHz_LPF") (class "Default")
      (node (ref "SW24") (pin "1") (pinfunction "IN1_1") (pintype "passive"))
      (node (ref "SW24") (pin "16") (pinfunction "S1_16") (pintype "passive"))
    )
    (net (code "7") (name "/10.2-11.4") (class "Default")
      (node (ref "SW4") (pin "1") (pinfunction "IN1_1") (pintype "passive"))
      (node (ref "SW4") (pin "16") (pinfunction "S1_16") (pintype "passive"))
    )
    (net (code "8") (name "/11.4-13.6") (class "Default")
      (node (ref "SW4") (pin "8") (pinfunction "IN4_8") (pintype "passive"))
      (node (ref "SW4") (pin "9") (pinfunction "IN3_9") (pintype "passive"))
    )
    (net (code "9") (name "/13.6-15.4") (class "Default")
      (node (ref "SW5") (pin "1") (pinfunction "IN1_1") (pintype "passive"))
      (node (ref "SW5") (pin "16") (pinfunction "S1_16") (pintype "passive"))
    )
    (net (code "10") (name "/15.4-18.6") (class "Default")
      (node (ref "SW5") (pin "8") (pinfunction "IN4_8") (pintype "passive"))
      (node (ref "SW5") (pin "9") (pinfunction "IN3_9") (pintype "passive"))
    )
    (net (code "11") (name "/20_GHz_LPF") (class "Default")
      (node (ref "SW24") (pin "8") (pinfunction "IN4_8") (pintype "passive"))
      (node (ref "SW24") (pin "9") (pinfunction "IN3_9") (pintype "passive"))
    )
    (net (code "12") (name "/22.5_GHz_IF") (class "Default")
      (node (ref "SW11") (pin "8") (pinfunction "IN4_8") (pintype "passive"))
      (node (ref "SW11") (pin "9") (pinfunction "IN3_9") (pintype "passive"))
    )
    (net (code "13") (name "/29.2_GHz_IF") (class "Default")
      (node (ref "SW11") (pin "1") (pinfunction "IN1_1") (pintype "passive"))
      (node (ref "SW11") (pin "16") (pinfunction "S1_16") (pintype "passive"))
    )
    (net (code "14") (name "/100ps") (class "Default")
      (node (ref "SW14") (pin "8") (pinfunction "IN4_8") (pintype "passive"))
      (node (ref "SW14") (pin "9") (pinfunction "IN3_9") (pintype "passive"))
    )
    (net (code "15") (name "/200ps") (class "Default")
      (node (ref "SW9") (pin "8") (pinfunction "IN4_8") (pintype "passive"))
      (node (ref "SW9") (pin "9") (pinfunction "IN3_9") (pintype "passive"))
    )
    (net (code "16") (name "/400ps_1") (class "Default")
      (node (ref "SW13") (pin "8") (pinfunction "IN4_8") (pintype "passive"))
      (node (ref "SW13") (pin "9") (pinfunction "IN3_9") (pintype "passive"))
    )
    (net (code "17") (name "/400ps_2") (class "Default")
      (node (ref "SW12") (pin "8") (pinfunction "IN4_8") (pintype "passive"))
      (node (ref "SW12") (pin "9") (pinfunction "IN3_9") (pintype "passive"))
    )
    (net (code "18") (name "/A1-A1_VVA_series") (class "Default")
      (node (ref "A1") (pin "T47") (pinfunction "T47_T47") (pintype "passive"))
    )
    (net (code "19") (name "/A1-A1_VVA_shunt") (class "Default")
      (node (ref "A1") (pin "T48") (pinfunction "T48_T48") (pintype "passive"))
    )
    (net (code "20") (name "/LOWER_LO") (class "Default")
      (node (ref "SW10") (pin "1") (pinfunction "IN1_1") (pintype "passive"))
      (node (ref "SW10") (pin "16") (pinfunction "S1_16") (pintype "passive"))
      (node (ref "SW22") (pin "1") (pinfunction "IN1_1") (pintype "passive"))
      (node (ref "SW22") (pin "16") (pinfunction "S1_16") (pintype "passive"))
    )
    (net (code "21") (name "/SRD_7.2") (class "Default")
      (node (ref "SW6") (pin "1") (pinfunction "IN1_1") (pintype "passive"))
      (node (ref "SW6") (pin "16") (pinfunction "S1_16") (pintype "passive"))
    )
    (net (code "22") (name "/SRD_8.4-9.6") (class "Default")
      (node (ref "SW6") (pin "8") (pinfunction "IN4_8") (pintype "passive"))
      (node (ref "SW6") (pin "9") (pinfunction "IN3_9") (pintype "passive"))
    )
    (net (code "23") (name "/SRD_10.8-12") (class "Default")
      (node (ref "SW7") (pin "1") (pinfunction "IN1_1") (pintype "passive"))
      (node (ref "SW7") (pin "16") (pinfunction "S1_16") (pintype "passive"))
    )
    (net (code "24") (name "/SRD_13.2-14.4") (class "Default")
      (node (ref "SW7") (pin "8") (pinfunction "IN4_8") (pintype "passive"))
      (node (ref "SW7") (pin "9") (pinfunction "IN3_9") (pintype "passive"))
    )
    (net (code "25") (name "/SRD_15.6-16.8") (class "Default")
      (node (ref "SW8") (pin "1") (pinfunction "IN1_1") (pintype "passive"))
      (node (ref "SW8") (pin "16") (pinfunction "S1_16") (pintype "passive"))
    )
    (net (code "26") (name "/SRD_18-19.2") (class "Default")
      (node (ref "SW8") (pin "8") (pinfunction "IN4_8") (pintype "passive"))
      (node (ref "SW8") (pin "9") (pinfunction "IN3_9") (pintype "passive"))
    )
    (net (code "27") (name "/SW301_2-1") (class "Default")
      (node (ref "A1") (pin "SW301-1") (pinfunction "SW301-1_SW301-1") (pintype "passive"))
      (node (ref "A1") (pin "SW302-1") (pinfunction "SW302-1_SW302-1") (pintype "passive"))
      (node (ref "SW301-1") (pin "1") (pintype "passive"))
      (node (ref "SW302-1") (pin "1") (pintype "passive"))
      (node (ref "SW6") (pin "15") (pinfunction "D2_15") (pintype "passive"))
      (node (ref "SW6") (pin "2") (pinfunction "D1_2") (pintype "passive"))
      (node (ref "TP25") (pin "1") (pinfunction "1_1") (pintype "passive"))
    )
    (net (code "28") (name "/SW301_2-2") (class "Default")
      (node (ref "A1") (pin "SW301-2") (pinfunction "SW301-2_SW301-2") (pintype "passive"))
      (node (ref "A1") (pin "SW302-2") (pinfunction "SW302-2_SW302-2") (pintype "passive"))
      (node (ref "SW301-2") (pin "1") (pintype "passive"))
      (node (ref "SW302-2") (pin "1") (pintype "passive"))
      (node (ref "SW6") (pin "10") (pinfunction "D3_10") (pintype "passive"))
      (node (ref "SW6") (pin "7") (pinfunction "D4_7") (pintype "passive"))
      (node (ref "TP30") (pin "1") (pinfunction "1_1") (pintype "passive"))
    )
    (net (code "29") (name "/SW301_2-3") (class "Default")
      (node (ref "A1") (pin "SW301-3") (pinfunction "SW301-3_SW301-3") (pintype "passive"))
      (node (ref "A1") (pin "SW302-3") (pinfunction "SW302-3_SW302-3") (pintype "passive"))
      (node (ref "SW301-3") (pin "1") (pintype "passive"))
      (node (ref "SW302-3") (pin "1") (pintype "passive"))
      (node (ref "SW8") (pin "10") (pinfunction "D3_10") (pintype "passive"))
      (node (ref "SW8") (pin "7") (pinfunction "D4_7") (pintype "passive"))
      (node (ref "TP36") (pin "1") (pinfunction "1_1") (pintype "passive"))
    )
    (net (code "30") (name "/SW301_2-4") (class "Default")
      (node (ref "A1") (pin "SW301-4") (pinfunction "SW301-4_SW301-4") (pintype "passive"))
      (node (ref "A1") (pin "SW302-4") (pinfunction "SW302-4_SW302-4") (pintype "passive"))
      (node (ref "SW301-4") (pin "1") (pintype "passive"))
      (node (ref "SW302-4") (pin "1") (pintype "passive"))
      (node (ref "SW8") (pin "15") (pinfunction "D2_15") (pintype "passive"))
      (node (ref "SW8") (pin "2") (pinfunction "D1_2") (pintype "passive"))
      (node (ref "TP32") (pin "1") (pinfunction "1_1") (pintype "passive"))
    )
    (net (code "31") (name "/SW301_2-5") (class "Default")
      (node (ref "A1") (pin "SW301-5") (pinfunction "SW301-5_SW301-5") (pintype "passive"))
      (node (ref "A1") (pin "SW302-5") (pinfunction "SW302-5_SW302-5") (pintype "passive"))
      (node (ref "SW301-5") (pin "1") (pintype "passive"))
      (node (ref "SW302-5") (pin "1") (pintype "passive"))
      (node (ref "SW7") (pin "10") (pinfunction "D3_10") (pintype "passive"))
      (node (ref "SW7") (pin "7") (pinfunction "D4_7") (pintype "passive"))
      (node (ref "TP35") (pin "1") (pinfunction "1_1") (pintype "passive"))
    )
    (net (code "32") (name "/SW301_2-6") (class "Default")
      (node (ref "A1") (pin "SW301-6") (pinfunction "SW301-6_SW301-6") (pintype "passive"))
      (node (ref "A1") (pin "SW302-6") (pinfunction "SW302-6_SW302-6") (pintype "passive"))
      (node (ref "SW301-6") (pin "1") (pintype "passive"))
      (node (ref "SW302-6") (pin "1") (pintype "passive"))
      (node (ref "SW7") (pin "15") (pinfunction "D2_15") (pintype "passive"))
      (node (ref "SW7") (pin "2") (pinfunction "D1_2") (pintype "passive"))
      (node (ref "TP31") (pin "1") (pinfunction "1_1") (pintype "passive"))
    )
    (net (code "33") (name "/SW303_4-1") (class "Default")
      (node (ref "A1") (pin "SW303-1") (pinfunction "SW303-1_SW303-1") (pintype "passive"))
      (node (ref "A1") (pin "SW304-1") (pinfunction "SW304-1_SW304-1") (pintype "passive"))
      (node (ref "SW3") (pin "15") (pinfunction "D2_15") (pintype "passive"))
      (node (ref "SW3") (pin "2") (pinfunction "D1_2") (pintype "passive"))
      (node (ref "SW303-1") (pin "1") (pintype "passive"))
      (node (ref "SW304-1") (pin "1") (pintype "passive"))
      (node (ref "TP21") (pin "1") (pinfunction "1_1") (pintype "passive"))
    )
    (net (code "34") (name "/SW303_4-2") (class "Default")
      (node (ref "A1") (pin "SW303-2") (pinfunction "SW303-2_SW303-2") (pintype "passive"))
      (node (ref "A1") (pin "SW304-2") (pinfunction "SW304-2_SW304-2") (pintype "passive"))
      (node (ref "SW3") (pin "10") (pinfunction "D3_10") (pintype "passive"))
      (node (ref "SW3") (pin "7") (pinfunction "D4_7") (pintype "passive"))
      (node (ref "SW303-2") (pin "1") (pintype "passive"))
      (node (ref "SW304-2") (pin "1") (pintype "passive"))
      (node (ref "TP27") (pin "1") (pinfunction "1_1") (pintype "passive"))
    )
    (net (code "35") (name "/SW303_4-3") (class "Default")
      (node (ref "A1") (pin "SW303-3") (pinfunction "SW303-3_SW303-3") (pintype "passive"))
      (node (ref "A1") (pin "SW304-3") (pinfunction "SW304-3_SW304-3") (pintype "passive"))
      (node (ref "SW303-3") (pin "1") (pintype "passive"))
      (node (ref "SW304-3") (pin "1") (pintype "passive"))
      (node (ref "SW4") (pin "10") (pinfunction "D3_10") (pintype "passive"))
      (node (ref "SW4") (pin "7") (pinfunction "D4_7") (pintype "passive"))
      (node (ref "TP28") (pin "1") (pinfunction "1_1") (pintype "passive"))
    )
    (net (code "36") (name "/SW303_4-4") (class "Default")
      (node (ref "A1") (pin "SW303-4") (pinfunction "SW303-4_SW303-4") (pintype "passive"))
      (node (ref "A1") (pin "SW304-4") (pinfunction "SW304-4_SW304-4") (pintype "passive"))
      (node (ref "SW303-4") (pin "1") (pintype "passive"))
      (node (ref "SW304-4") (pin "1") (pintype "passive"))
      (node (ref "SW5") (pin "10") (pinfunction "D3_10") (pintype "passive"))
      (node (ref "SW5") (pin "7") (pinfunction "D4_7") (pintype "passive"))
      (node (ref "TP29") (pin "1") (pinfunction "1_1") (pintype "passive"))
    )
    (net (code "37") (name "/SW303_4-5") (class "Default")
      (node (ref "A1") (pin "SW303-5") (pinfunction "SW303-5_SW303-5") (pintype "passive"))
      (node (ref "A1") (pin "SW304-5") (pinfunction "SW304-5_SW304-5") (pintype "passive"))
      (node (ref "SW303-5") (pin "1") (pintype "passive"))
      (node (ref "SW304-5") (pin "1") (pintype "passive"))
      (node (ref "SW5") (pin "15") (pinfunction "D2_15") (pintype "passive"))
      (node (ref "SW5") (pin "2") (pinfunction "D1_2") (pintype "passive"))
      (node (ref "TP23") (pin "1") (pinfunction "1_1") (pintype "passive"))
    )
    (net (code "38") (name "/SW303_4-6") (class "Default")
      (node (ref "A1") (pin "SW303-6") (pinfunction "SW303-6_SW303-6") (pintype "passive"))
      (node (ref "A1") (pin "SW304-6") (pinfunction "SW304-6_SW304-6") (pintype "passive"))
      (node (ref "SW303-6") (pin "1") (pintype "passive"))
      (node (ref "SW304-6") (pin "1") (pintype "passive"))
      (node (ref "SW4") (pin "15") (pinfunction "D2_15") (pintype "passive"))
      (node (ref "SW4") (pin "2") (pinfunction "D1_2") (pintype "passive"))
      (node (ref "TP22") (pin "1") (pinfunction "1_1") (pintype "passive"))
    )
    (net (code "39") (name "/T1") (class "Default")
      (node (ref "A1") (pin "T1") (pinfunction "T1_T1") (pintype "passive"))
    )
    (net (code "40") (name "/T14") (class "Default")
      (node (ref "A1") (pin "T14") (pinfunction "T14_T14") (pintype "passive"))
    )
    (net (code "41") (name "/T15") (class "Default")
      (node (ref "A1") (pin "T15") (pinfunction "T15_T15") (pintype "passive"))
    )
    (net (code "42") (name "/T16") (class "Default")
      (node (ref "A1") (pin "T16") (pinfunction "T16_T16") (pintype "passive"))
    )
    (net (code "43") (name "/T17") (class "Default")
      (node (ref "A1") (pin "T17") (pinfunction "T17_T17") (pintype "passive"))
    )
    (net (code "44") (name "/T18_21") (class "Default")
      (node (ref "A1") (pin "T18") (pinfunction "T18_T18") (pintype "passive"))
      (node (ref "A1") (pin "T21") (pinfunction "T21_T21") (pintype "passive"))
      (node (ref "SW14") (pin "10") (pinfunction "D3_10") (pintype "passive"))
      (node (ref "SW14") (pin "7") (pinfunction "D4_7") (pintype "passive"))
      (node (ref "T18") (pin "1") (pintype "passive"))
      (node (ref "T21") (pin "1") (pintype "passive"))
      (node (ref "TP45") (pin "1") (pinfunction "1_1") (pintype "passive"))
    )
    (net (code "45") (name "/T19_20") (class "Default")
      (node (ref "A1") (pin "T19") (pinfunction "T19_T19") (pintype "passive"))
      (node (ref "A1") (pin "T20") (pinfunction "T20_T20") (pintype "passive"))
      (node (ref "SW14") (pin "15") (pinfunction "D2_15") (pintype "passive"))
      (node (ref "SW14") (pin "2") (pinfunction "D1_2") (pintype "passive"))
      (node (ref "T19") (pin "1") (pintype "passive"))
      (node (ref "T20") (pin "1") (pintype "passive"))
      (node (ref "TP40") (pin "1") (pinfunction "1_1") (pintype "passive"))
    )
    (net (code "46") (name "/T22_25") (class "Default")
      (node (ref "A1") (pin "T22") (pinfunction "T22_T22") (pintype "passive"))
      (node (ref "A1") (pin "T25") (pinfunction "T25_T25") (pintype "passive"))
      (node (ref "SW12") (pin "10") (pinfunction "D3_10") (pintype "passive"))
      (node (ref "SW12") (pin "7") (pinfunction "D4_7") (pintype "passive"))
      (node (ref "T22") (pin "1") (pintype "passive"))
      (node (ref "T25") (pin "1") (pintype "passive"))
      (node (ref "TP44") (pin "1") (pinfunction "1_1") (pintype "passive"))
    )
    (net (code "47") (name "/T23_24") (class "Default")
      (node (ref "A1") (pin "T23") (pinfunction "T23_T23") (pintype "passive"))
      (node (ref "A1") (pin "T24") (pinfunction "T24_T24") (pintype "passive"))
      (node (ref "SW12") (pin "15") (pinfunction "D2_15") (pintype "passive"))
      (node (ref "SW12") (pin "2") (pinfunction "D1_2") (pintype "passive"))
      (node (ref "T23") (pin "1") (pintype "passive"))
      (node (ref "T24") (pin "1") (pintype "passive"))
      (node (ref "TP39") (pin "1") (pinfunction "1_1") (pintype "passive"))
    )
    (net (code "48") (name "/T26_29") (class "Default")
      (node (ref "A1") (pin "T26") (pinfunction "T26_T26") (pintype "passive"))
      (node (ref "A1") (pin "T29") (pinfunction "T29_T29") (pintype "passive"))
      (node (ref "SW13") (pin "10") (pinfunction "D3_10") (pintype "passive"))
      (node (ref "SW13") (pin "7") (pinfunction "D4_7") (pintype "passive"))
      (node (ref "T26") (pin "1") (pintype "passive"))
      (node (ref "T29") (pin "1") (pintype "passive"))
      (node (ref "TP38") (pin "1") (pinfunction "1_1") (pintype "passive"))
    )
    (net (code "49") (name "/T27_28") (class "Default")
      (node (ref "A1") (pin "T27") (pinfunction "T27_T27") (pintype "passive"))
      (node (ref "A1") (pin "T28") (pinfunction "T28_T28") (pintype "passive"))
      (node (ref "SW13") (pin "15") (pinfunction "D2_15") (pintype "passive"))
      (node (ref "SW13") (pin "2") (pinfunction "D1_2") (pintype "passive"))
      (node (ref "T27") (pin "1") (pintype "passive"))
      (node (ref "T28") (pin "1") (pintype "passive"))
      (node (ref "TP34") (pin "1") (pinfunction "1_1") (pintype "passive"))
    )
    (net (code "50") (name "/T30_33") (class "Default")
      (node (ref "A1") (pin "T30") (pinfunction "T30_T30") (pintype "passive"))
      (node (ref "A1") (pin "T33") (pinfunction "T33_T33") (pintype "passive"))
      (node (ref "SW9") (pin "10") (pinfunction "D3_10") (pintype "passive"))
      (node (ref "SW9") (pin "7") (pinfunction "D4_7") (pintype "passive"))
      (node (ref "T30") (pin "1") (pintype "passive"))
      (node (ref "T33") (pin "1") (pintype "passive"))
      (node (ref "TP37") (pin "1") (pinfunction "1_1") (pintype "passive"))
    )
    (net (code "51") (name "/T31_32") (class "Default")
      (node (ref "A1") (pin "T31") (pinfunction "T31_T31") (pintype "passive"))
      (node (ref "A1") (pin "T32") (pinfunction "T32_T32") (pintype "passive"))
      (node (ref "SW9") (pin "15") (pinfunction "D2_15") (pintype "passive"))
      (node (ref "SW9") (pin "2") (pinfunction "D1_2") (pintype "passive"))
      (node (ref "T31") (pin "1") (pintype "passive"))
      (node (ref "T32") (pin "1") (pintype "passive"))
      (node (ref "TP33") (pin "1") (pinfunction "1_1") (pintype "passive"))
    )
    (net (code "52") (name "/T34") (class "Default")
      (node (ref "A1") (pin "T34") (pinfunction "T34_T34") (pintype "passive"))
    )
    (net (code "53") (name "/T35") (class "Default")
      (node (ref "A1") (pin "T35") (pinfunction "T35_T35") (pintype "passive"))
    )
    (net (code "54") (name "/T36") (class "Default")
      (node (ref "A1") (pin "T36") (pinfunction "T36_T36") (pintype "passive"))
    )
    (net (code "55") (name "/T37") (class "Default")
      (node (ref "A1") (pin "T37") (pinfunction "T37_T37") (pintype "passive"))
    )
    (net (code "56") (name "/T38") (class "Default")
      (node (ref "A1") (pin "T38") (pinfunction "T38_T38") (pintype "passive"))
    )
    (net (code "57") (name "/T39") (class "Default")
      (node (ref "A1") (pin "T39") (pinfunction "T39_T39") (pintype "passive"))
    )
    (net (code "58") (name "/T40") (class "Default")
      (node (ref "A1") (pin "T40") (pinfunction "T40_T40") (pintype "passive"))
    )
    (net (code "59") (name "/T41_46") (class "Default")
      (node (ref "A1") (pin "T41") (pinfunction "T41_T41") (pintype "passive"))
      (node (ref "A1") (pin "T46") (pinfunction "T46_T46") (pintype "passive"))
      (node (ref "SW11") (pin "10") (pinfunction "D3_10") (pintype "passive"))
      (node (ref "SW11") (pin "7") (pinfunction "D4_7") (pintype "passive"))
      (node (ref "T41") (pin "1") (pintype "passive"))
      (node (ref "T46") (pin "1") (pintype "passive"))
      (node (ref "TP46") (pin "1") (pinfunction "1_1") (pintype "passive"))
    )
    (net (code "60") (name "/T42_45") (class "Default")
      (node (ref "A1") (pin "T42") (pinfunction "T42_T42") (pintype "passive"))
      (node (ref "A1") (pin "T45") (pinfunction "T45_T45") (pintype "passive"))
      (node (ref "SW11") (pin "15") (pinfunction "D2_15") (pintype "passive"))
      (node (ref "SW11") (pin "2") (pinfunction "D1_2") (pintype "passive"))
      (node (ref "T42") (pin "1") (pintype "passive"))
      (node (ref "T45") (pin "1") (pintype "passive"))
      (node (ref "TP41") (pin "1") (pinfunction "1_1") (pintype "passive"))
    )
    (net (code "61") (name "/T43") (class "Default")
      (node (ref "A1") (pin "T43") (pinfunction "T43_T43") (pintype "passive"))
    )
    (net (code "62") (name "/T44") (class "Default")
      (node (ref "A1") (pin "T44") (pinfunction "T44_T44") (pintype "passive"))
    )
    (net (code "63") (name "/T49") (class "Default")
      (node (ref "A1") (pin "T49") (pinfunction "T49_T49") (pintype "passive"))
    )
    (net (code "64") (name "/T50") (class "Default")
      (node (ref "A1") (pin "T50") (pinfunction "T50_T50") (pintype "passive"))
    )
    (net (code "65") (name "/T51") (class "Default")
      (node (ref "A1") (pin "T51") (pinfunction "T51_T51") (pintype "passive"))
    )
    (net (code "66") (name "/T52") (class "Default")
      (node (ref "A1") (pin "T52") (pinfunction "T52_T52") (pintype "passive"))
    )
    (net (code "67") (name "/T53") (class "Default")
      (node (ref "A1") (pin "T53") (pinfunction "T53_T53") (pintype "passive"))
    )
    (net (code "68") (name "/T54") (class "Default")
      (node (ref "A1") (pin "T54") (pinfunction "T54_T54") (pintype "passive"))
    )
    (net (code "69") (name "/T55") (class "Default")
      (node (ref "A1") (pin "T55") (pinfunction "T55_T55") (pintype "passive"))
    )
    (net (code "70") (name "/T62") (class "Default")
      (node (ref "A1") (pin "T62") (pinfunction "T62_T62") (pintype "passive"))
      (node (ref "SW24") (pin "10") (pinfunction "D3_10") (pintype "passive"))
      (node (ref "SW24") (pin "7") (pinfunction "D4_7") (pintype "passive"))
      (node (ref "T62") (pin "1") (pintype "passive"))
      (node (ref "TP26") (pin "1") (pinfunction "1_1") (pintype "passive"))
    )
    (net (code "71") (name "/T63") (class "Default")
      (node (ref "A1") (pin "T63") (pinfunction "T63_T63") (pintype "passive"))
      (node (ref "SW24") (pin "15") (pinfunction "D2_15") (pintype "passive"))
      (node (ref "SW24") (pin "2") (pinfunction "D1_2") (pintype "passive"))
      (node (ref "T63") (pin "1") (pintype "passive"))
      (node (ref "TP24") (pin "1") (pinfunction "1_1") (pintype "passive"))
    )
    (net (code "72") (name "/T70") (class "Default")
      (node (ref "A1") (pin "T70") (pinfunction "T70_T70") (pintype "passive"))
    )
    (net (code "73") (name "/T71") (class "Default")
      (node (ref "A1") (pin "T71") (pinfunction "T71_T71") (pintype "passive"))
    )
    (net (code "74") (name "/T72") (class "Default")
      (node (ref "A1") (pin "T72") (pinfunction "T72_T72") (pintype "passive"))
    )
    (net (code "75") (name "/T73_76") (class "Default")
      (node (ref "A1") (pin "T73") (pinfunction "T73_T73") (pintype "passive"))
      (node (ref "A1") (pin "T76") (pinfunction "T76_T76") (pintype "passive"))
      (node (ref "SW22") (pin "15") (pinfunction "D2_15") (pintype "passive"))
      (node (ref "SW22") (pin "2") (pinfunction "D1_2") (pintype "passive"))
      (node (ref "T73") (pin "1") (pintype "passive"))
      (node (ref "T76") (pin "1") (pintype "passive"))
      (node (ref "TP43") (pin "1") (pinfunction "1_1") (pintype "passive"))
    )
    (net (code "76") (name "/T74_75") (class "Default")
      (node (ref "A1") (pin "T74") (pinfunction "T74_T74") (pintype "passive"))
      (node (ref "A1") (pin "T75") (pinfunction "T75_T75") (pintype "passive"))
      (node (ref "SW22") (pin "10") (pinfunction "D3_10") (pintype "passive"))
      (node (ref "SW22") (pin "7") (pinfunction "D4_7") (pintype "passive"))
      (node (ref "T74") (pin "1") (pintype "passive"))
      (node (ref "T75") (pin "1") (pintype "passive"))
      (node (ref "TP48") (pin "1") (pinfunction "1_1") (pintype "passive"))
    )
    (net (code "77") (name "/T77") (class "Default")
      (node (ref "A1") (pin "T77") (pinfunction "T77_T77") (pintype "passive"))
    )
    (net (code "78") (name "/T78") (class "Default")
      (node (ref "A1") (pin "T78") (pinfunction "T78_T78") (pintype "passive"))
    )
    (net (code "79") (name "/T79") (class "Default")
      (node (ref "A1") (pin "T79") (pinfunction "T79_T79") (pintype "passive"))
    )
    (net (code "80") (name "/T80_83") (class "Default")
      (node (ref "A1") (pin "T80") (pinfunction "T80_T80") (pintype "passive"))
      (node (ref "A1") (pin "T83") (pinfunction "T83_T83") (pintype "passive"))
      (node (ref "SW10") (pin "15") (pinfunction "D2_15") (pintype "passive"))
      (node (ref "SW10") (pin "2") (pinfunction "D1_2") (pintype "passive"))
      (node (ref "T80") (pin "1") (pintype "passive"))
      (node (ref "T83") (pin "1") (pintype "passive"))
      (node (ref "TP42") (pin "1") (pinfunction "1_1") (pintype "passive"))
    )
    (net (code "81") (name "/T81_82") (class "Default")
      (node (ref "A1") (pin "T81") (pinfunction "T81_T81") (pintype "passive"))
      (node (ref "A1") (pin "T82") (pinfunction "T82_T82") (pintype "passive"))
      (node (ref "SW10") (pin "10") (pinfunction "D3_10") (pintype "passive"))
      (node (ref "SW10") (pin "7") (pinfunction "D4_7") (pintype "passive"))
      (node (ref "T81") (pin "1") (pintype "passive"))
      (node (ref "T82") (pin "1") (pintype "passive"))
      (node (ref "TP47") (pin "1") (pinfunction "1_1") (pintype "passive"))
    )
    (net (code "82") (name "/T84") (class "Default")
      (node (ref "A1") (pin "T84") (pinfunction "T84_T84") (pintype "passive"))
    )
    (net (code "83") (name "/UPPER_LO") (class "Default")
      (node (ref "SW10") (pin "8") (pinfunction "IN4_8") (pintype "passive"))
      (node (ref "SW10") (pin "9") (pinfunction "IN3_9") (pintype "passive"))
      (node (ref "SW22") (pin "8") (pinfunction "IN4_8") (pintype "passive"))
      (node (ref "SW22") (pin "9") (pinfunction "IN3_9") (pintype "passive"))
    )
    (net (code "84") (name "/~{100ps}") (class "Default")
      (node (ref "SW14") (pin "1") (pinfunction "IN1_1") (pintype "passive"))
      (node (ref "SW14") (pin "16") (pinfunction "S1_16") (pintype "passive"))
    )
    (net (code "85") (name "/~{200ps}") (class "Default")
      (node (ref "SW9") (pin "1") (pinfunction "IN1_1") (pintype "passive"))
      (node (ref "SW9") (pin "16") (pinfunction "S1_16") (pintype "passive"))
    )
    (net (code "86") (name "/~{400ps_1}") (class "Default")
      (node (ref "SW13") (pin "1") (pinfunction "IN1_1") (pintype "passive"))
      (node (ref "SW13") (pin "16") (pinfunction "S1_16") (pintype "passive"))
    )
    (net (code "87") (name "/~{400ps_2}") (class "Default")
      (node (ref "SW12") (pin "1") (pinfunction "IN1_1") (pintype "passive"))
      (node (ref "SW12") (pin "16") (pinfunction "S1_16") (pintype "passive"))
    )
    (net (code "88") (name "GND") (class "Default")
      (node (ref "A1") (pin "A1-A1_shield") (pinfunction "shield_A1-A1_shield") (pintype "passive"))
      (node (ref "A1") (pin "MH1") (pinfunction "MH1_MH1") (pintype "passive"))
      (node (ref "C130") (pin "1") (pintype "passive"))
      (node (ref "C131") (pin "1") (pintype "passive"))
      (node (ref "C132") (pin "1") (pintype "passive"))
      (node (ref "C133") (pin "1") (pintype "passive"))
      (node (ref "C134") (pin "1") (pintype "passive"))
      (node (ref "C135") (pin "1") (pintype "passive"))
      (node (ref "C136") (pin "1") (pintype "passive"))
      (node (ref "C137") (pin "1") (pintype "passive"))
      (node (ref "C138") (pin "1") (pintype "passive"))
      (node (ref "C154") (pin "1") (pintype "passive"))
      (node (ref "C574") (pin "1") (pintype "passive"))
      (node (ref "C582") (pin "1") (pintype "passive"))
      (node (ref "C583") (pin "1") (pintype "passive"))
      (node (ref "C584") (pin "1") (pintype "passive"))
      (node (ref "C585") (pin "1") (pintype "passive"))
      (node (ref "C627") (pin "1") (pintype "passive"))
      (node (ref "C628") (pin "1") (pintype "passive"))
      (node (ref "C629") (pin "1") (pintype "passive"))
      (node (ref "C630") (pin "1") (pintype "passive"))
      (node (ref "C631") (pin "1") (pintype "passive"))
      (node (ref "C632") (pin "1") (pintype "passive"))
      (node (ref "C633") (pin "1") (pintype "passive"))
      (node (ref "C634") (pin "1") (pintype "passive"))
      (node (ref "C635") (pin "1") (pintype "passive"))
      (node (ref "C636") (pin "1") (pintype "passive"))
      (node (ref "C637") (pin "1") (pintype "passive"))
      (node (ref "C638") (pin "1") (pintype "passive"))
      (node (ref "C639") (pin "1") (pintype "passive"))
      (node (ref "C640") (pin "1") (pintype "passive"))
      (node (ref "C641") (pin "1") (pintype "passive"))
      (node (ref "C642") (pin "1") (pintype "passive"))
      (node (ref "C643") (pin "1") (pintype "passive"))
      (node (ref "C644") (pin "1") (pintype "passive"))
      (node (ref "C645") (pin "1") (pintype "passive"))
      (node (ref "C646") (pin "1") (pintype "passive"))
      (node (ref "C647") (pin "1") (pintype "passive"))
      (node (ref "C648") (pin "1") (pintype "passive"))
      (node (ref "C649") (pin "1") (pintype "passive"))
      (node (ref "C650") (pin "1") (pintype "passive"))
      (node (ref "C651") (pin "1") (pintype "passive"))
      (node (ref "C652") (pin "1") (pintype "passive"))
      (node (ref "C653") (pin "1") (pintype "passive"))
      (node (ref "C655") (pin "1") (pintype "passive"))
      (node (ref "C656") (pin "1") (pintype "passive"))
      (node (ref "C657") (pin "1") (pintype "passive"))
      (node (ref "C658") (pin "1") (pintype "passive"))
      (node (ref "C659") (pin "1") (pintype "passive"))
      (node (ref "C660") (pin "1") (pintype "passive"))
      (node (ref "C661") (pin "1") (pintype "passive"))
      (node (ref "C662") (pin "1") (pintype "passive"))
      (node (ref "C663") (pin "1") (pintype "passive"))
      (node (ref "C664") (pin "1") (pintype "passive"))
      (node (ref "C665") (pin "2") (pintype "passive"))
      (node (ref "C666") (pin "2") (pintype "passive"))
      (node (ref "C667") (pin "2") (pintype "passive"))
      (node (ref "C668") (pin "2") (pintype "passive"))
      (node (ref "C669") (pin "2") (pintype "passive"))
      (node (ref "C670") (pin "2") (pintype "passive"))
      (node (ref "C671") (pin "2") (pintype "passive"))
      (node (ref "C672") (pin "2") (pintype "passive"))
      (node (ref "C673") (pin "1") (pintype "passive"))
      (node (ref "C674") (pin "1") (pintype "passive"))
      (node (ref "C675") (pin "1") (pintype "passive"))
      (node (ref "C676") (pin "1") (pintype "passive"))
      (node (ref "C677") (pin "1") (pintype "passive"))
      (node (ref "C678") (pin "1") (pintype "passive"))
      (node (ref "C679") (pin "1") (pintype "passive"))
      (node (ref "C680") (pin "1") (pintype "passive"))
      (node (ref "C681") (pin "2") (pintype "passive"))
      (node (ref "C682") (pin "2") (pintype "passive"))
      (node (ref "C683") (pin "2") (pintype "passive"))
      (node (ref "C684") (pin "2") (pintype "passive"))
      (node (ref "C685") (pin "1") (pintype "passive"))
      (node (ref "C686") (pin "1") (pintype "passive"))
      (node (ref "C687") (pin "1") (pintype "passive"))
      (node (ref "C688") (pin "1") (pintype "passive"))
      (node (ref "C689") (pin "1") (pintype "passive"))
      (node (ref "C690") (pin "1") (pintype "passive"))
      (node (ref "C691") (pin "1") (pintype "passive"))
      (node (ref "C692") (pin "1") (pintype "passive"))
      (node (ref "C693") (pin "1") (pintype "passive"))
      (node (ref "C694") (pin "1") (pintype "passive"))
      (node (ref "C695") (pin "1") (pintype "passive"))
      (node (ref "C696") (pin "1") (pintype "passive"))
      (node (ref "C697") (pin "2") (pintype "passive"))
      (node (ref "C698") (pin "1") (pintype "passive"))
      (node (ref "C699") (pin "1") (pintype "passive"))
      (node (ref "C700") (pin "2") (pintype "passive"))
      (node (ref "C701") (pin "1") (pintype "passive"))
      (node (ref "C702") (pin "1") (pintype "passive"))
      (node (ref "C703") (pin "1") (pintype "passive"))
      (node (ref "C704") (pin "1") (pintype "passive"))
      (node (ref "C705") (pin "1") (pintype "passive"))
      (node (ref "C706") (pin "1") (pintype "passive"))
      (node (ref "C707") (pin "1") (pintype "passive"))
      (node (ref "C708") (pin "1") (pintype "passive"))
      (node (ref "C709") (pin "1") (pintype "passive"))
      (node (ref "C710") (pin "1") (pintype "passive"))
      (node (ref "SW10") (pin "5") (pinfunction "IN2_5") (pintype "passive"))
      (node (ref "SW11") (pin "5") (pinfunction "IN2_5") (pintype "passive"))
      (node (ref "SW12") (pin "5") (pinfunction "IN2_5") (pintype "passive"))
      (node (ref "SW13") (pin "5") (pinfunction "IN2_5") (pintype "passive"))
      (node (ref "SW14") (pin "5") (pinfunction "IN2_5") (pintype "passive"))
      (node (ref "SW22") (pin "5") (pinfunction "IN2_5") (pintype "passive"))
      (node (ref "SW24") (pin "5") (pinfunction "IN2_5") (pintype "passive"))
      (node (ref "SW3") (pin "5") (pinfunction "IN2_5") (pintype "passive"))
      (node (ref "SW4") (pin "5") (pinfunction "IN2_5") (pintype "passive"))
      (node (ref "SW5") (pin "5") (pinfunction "IN2_5") (pintype "passive"))
      (node (ref "SW6") (pin "5") (pinfunction "IN2_5") (pintype "passive"))
      (node (ref "SW7") (pin "5") (pinfunction "IN2_5") (pintype "passive"))
      (node (ref "SW8") (pin "5") (pinfunction "IN2_5") (pintype "passive"))
      (node (ref "SW9") (pin "5") (pinfunction "IN2_5") (pintype "passive"))
    )
    (net (code "89") (name "Net-(R109-Pad1)") (class "Default")
      (node (ref "R109") (pin "1") (pintype "passive"))
      (node (ref "SW3") (pin "3") (pinfunction "S1_3") (pintype "passive"))
    )
    (net (code "90") (name "Net-(R110-Pad1)") (class "Default")
      (node (ref "R110") (pin "1") (pintype "passive"))
      (node (ref "SW4") (pin "3") (pinfunction "S1_3") (pintype "passive"))
    )
    (net (code "91") (name "Net-(R111-Pad1)") (class "Default")
      (node (ref "R111") (pin "1") (pintype "passive"))
      (node (ref "SW5") (pin "3") (pinfunction "S1_3") (pintype "passive"))
    )
    (net (code "92") (name "Net-(R116-Pad1)") (class "Default")
      (node (ref "R116") (pin "1") (pintype "passive"))
      (node (ref "SW7") (pin "3") (pinfunction "S1_3") (pintype "passive"))
    )
    (net (code "93") (name "Net-(R130-Pad1)") (class "Default")
      (node (ref "R130") (pin "1") (pintype "passive"))
      (node (ref "SW9") (pin "3") (pinfunction "S1_3") (pintype "passive"))
    )
    (net (code "94") (name "Net-(R132-Pad1)") (class "Default")
      (node (ref "R132") (pin "1") (pintype "passive"))
      (node (ref "SW22") (pin "3") (pinfunction "S1_3") (pintype "passive"))
    )
    (net (code "95") (name "Net-(R134-Pad1)") (class "Default")
      (node (ref "R134") (pin "1") (pintype "passive"))
      (node (ref "SW6") (pin "3") (pinfunction "S1_3") (pintype "passive"))
    )
    (net (code "96") (name "Net-(R135-Pad1)") (class "Default")
      (node (ref "R135") (pin "1") (pintype "passive"))
      (node (ref "SW8") (pin "3") (pinfunction "S1_3") (pintype "passive"))
    )
    (net (code "97") (name "Net-(R148-Pad1)") (class "Default")
      (node (ref "R148") (pin "1") (pintype "passive"))
      (node (ref "SW11") (pin "3") (pinfunction "S1_3") (pintype "passive"))
    )
    (net (code "98") (name "Net-(R149-Pad1)") (class "Default")
      (node (ref "R149") (pin "1") (pintype "passive"))
      (node (ref "SW12") (pin "3") (pinfunction "S1_3") (pintype "passive"))
    )
    (net (code "99") (name "Net-(R150-Pad1)") (class "Default")
      (node (ref "R150") (pin "1") (pintype "passive"))
      (node (ref "SW13") (pin "3") (pinfunction "S1_3") (pintype "passive"))
    )
    (net (code "100") (name "Net-(R151-Pad1)") (class "Default")
      (node (ref "R151") (pin "1") (pintype "passive"))
      (node (ref "SW14") (pin "3") (pinfunction "S1_3") (pintype "passive"))
    )
    (net (code "101") (name "Net-(R246-Pad1)") (class "Default")
      (node (ref "R246") (pin "1") (pintype "passive"))
      (node (ref "SW10") (pin "3") (pinfunction "S1_3") (pintype "passive"))
    )
    (net (code "102") (name "Net-(R349-Pad1)") (class "Default")
      (node (ref "R349") (pin "1") (pintype "passive"))
      (node (ref "SW24") (pin "3") (pinfunction "S1_3") (pintype "passive"))
    )
    (net (code "103") (name "Net-(SW3-S2)") (class "Default")
      (node (ref "R117") (pin "1") (pintype "passive"))
      (node (ref "SW3") (pin "14") (pinfunction "S2_14") (pintype "passive"))
    )
    (net (code "104") (name "Net-(SW3-S3)") (class "Default")
      (node (ref "R122") (pin "1") (pintype "passive"))
      (node (ref "SW3") (pin "11") (pinfunction "S3_11") (pintype "passive"))
    )
    (net (code "105") (name "Net-(SW3-S4)") (class "Default")
      (node (ref "R126") (pin "1") (pintype "passive"))
      (node (ref "SW3") (pin "6") (pinfunction "S4_6") (pintype "passive"))
    )
    (net (code "106") (name "Net-(SW4-S2)") (class "Default")
      (node (ref "R119") (pin "1") (pintype "passive"))
      (node (ref "SW4") (pin "14") (pinfunction "S2_14") (pintype "passive"))
    )
    (net (code "107") (name "Net-(SW4-S3)") (class "Default")
      (node (ref "R123") (pin "1") (pintype "passive"))
      (node (ref "SW4") (pin "11") (pinfunction "S3_11") (pintype "passive"))
    )
    (net (code "108") (name "Net-(SW4-S4)") (class "Default")
      (node (ref "R127") (pin "1") (pintype "passive"))
      (node (ref "SW4") (pin "6") (pinfunction "S4_6") (pintype "passive"))
    )
    (net (code "109") (name "Net-(SW5-S2)") (class "Default")
      (node (ref "R120") (pin "1") (pintype "passive"))
      (node (ref "SW5") (pin "14") (pinfunction "S2_14") (pintype "passive"))
    )
    (net (code "110") (name "Net-(SW5-S3)") (class "Default")
      (node (ref "R124") (pin "1") (pintype "passive"))
      (node (ref "SW5") (pin "11") (pinfunction "S3_11") (pintype "passive"))
    )
    (net (code "111") (name "Net-(SW5-S4)") (class "Default")
      (node (ref "R128") (pin "1") (pintype "passive"))
      (node (ref "SW5") (pin "6") (pinfunction "S4_6") (pintype "passive"))
    )
    (net (code "112") (name "Net-(SW6-S2)") (class "Default")
      (node (ref "R138") (pin "1") (pintype "passive"))
      (node (ref "SW6") (pin "14") (pinfunction "S2_14") (pintype "passive"))
    )
    (net (code "113") (name "Net-(SW6-S3)") (class "Default")
      (node (ref "R142") (pin "1") (pintype "passive"))
      (node (ref "SW6") (pin "11") (pinfunction "S3_11") (pintype "passive"))
    )
    (net (code "114") (name "Net-(SW6-S4)") (class "Default")
      (node (ref "R146") (pin "1") (pintype "passive"))
      (node (ref "SW6") (pin "6") (pinfunction "S4_6") (pintype "passive"))
    )
    (net (code "115") (name "Net-(SW7-S2)") (class "Default")
      (node (ref "R121") (pin "1") (pintype "passive"))
      (node (ref "SW7") (pin "14") (pinfunction "S2_14") (pintype "passive"))
    )
    (net (code "116") (name "Net-(SW7-S3)") (class "Default")
      (node (ref "R125") (pin "1") (pintype "passive"))
      (node (ref "SW7") (pin "11") (pinfunction "S3_11") (pintype "passive"))
    )
    (net (code "117") (name "Net-(SW7-S4)") (class "Default")
      (node (ref "R129") (pin "1") (pintype "passive"))
      (node (ref "SW7") (pin "6") (pinfunction "S4_6") (pintype "passive"))
    )
    (net (code "118") (name "Net-(SW8-S2)") (class "Default")
      (node (ref "R139") (pin "1") (pintype "passive"))
      (node (ref "SW8") (pin "14") (pinfunction "S2_14") (pintype "passive"))
    )
    (net (code "119") (name "Net-(SW8-S3)") (class "Default")
      (node (ref "R143") (pin "1") (pintype "passive"))
      (node (ref "SW8") (pin "11") (pinfunction "S3_11") (pintype "passive"))
    )
    (net (code "120") (name "Net-(SW8-S4)") (class "Default")
      (node (ref "R147") (pin "1") (pintype "passive"))
      (node (ref "SW8") (pin "6") (pinfunction "S4_6") (pintype "passive"))
    )
    (net (code "121") (name "Net-(SW9-S2)") (class "Default")
      (node (ref "R136") (pin "1") (pintype "passive"))
      (node (ref "SW9") (pin "14") (pinfunction "S2_14") (pintype "passive"))
    )
    (net (code "122") (name "Net-(SW9-S3)") (class "Default")
      (node (ref "R140") (pin "1") (pintype "passive"))
      (node (ref "SW9") (pin "11") (pinfunction "S3_11") (pintype "passive"))
    )
    (net (code "123") (name "Net-(SW9-S4)") (class "Default")
      (node (ref "R144") (pin "1") (pintype "passive"))
      (node (ref "SW9") (pin "6") (pinfunction "S4_6") (pintype "passive"))
    )
    (net (code "124") (name "Net-(SW10-S2)") (class "Default")
      (node (ref "R137") (pin "1") (pintype "passive"))
      (node (ref "SW10") (pin "14") (pinfunction "S2_14") (pintype "passive"))
    )
    (net (code "125") (name "Net-(SW10-S3)") (class "Default")
      (node (ref "R141") (pin "1") (pintype "passive"))
      (node (ref "SW10") (pin "11") (pinfunction "S3_11") (pintype "passive"))
    )
    (net (code "126") (name "Net-(SW10-S4)") (class "Default")
      (node (ref "R145") (pin "1") (pintype "passive"))
      (node (ref "SW10") (pin "6") (pinfunction "S4_6") (pintype "passive"))
    )
    (net (code "127") (name "Net-(SW11-S2)") (class "Default")
      (node (ref "R152") (pin "1") (pintype "passive"))
      (node (ref "SW11") (pin "14") (pinfunction "S2_14") (pintype "passive"))
    )
    (net (code "128") (name "Net-(SW11-S3)") (class "Default")
      (node (ref "R156") (pin "1") (pintype "passive"))
      (node (ref "SW11") (pin "11") (pinfunction "S3_11") (pintype "passive"))
    )
    (net (code "129") (name "Net-(SW11-S4)") (class "Default")
      (node (ref "R160") (pin "1") (pintype "passive"))
      (node (ref "SW11") (pin "6") (pinfunction "S4_6") (pintype "passive"))
    )
    (net (code "130") (name "Net-(SW12-S2)") (class "Default")
      (node (ref "R153") (pin "1") (pintype "passive"))
      (node (ref "SW12") (pin "14") (pinfunction "S2_14") (pintype "passive"))
    )
    (net (code "131") (name "Net-(SW12-S3)") (class "Default")
      (node (ref "R157") (pin "1") (pintype "passive"))
      (node (ref "SW12") (pin "11") (pinfunction "S3_11") (pintype "passive"))
    )
    (net (code "132") (name "Net-(SW12-S4)") (class "Default")
      (node (ref "R161") (pin "1") (pintype "passive"))
      (node (ref "SW12") (pin "6") (pinfunction "S4_6") (pintype "passive"))
    )
    (net (code "133") (name "Net-(SW13-S2)") (class "Default")
      (node (ref "R154") (pin "1") (pintype "passive"))
      (node (ref "SW13") (pin "14") (pinfunction "S2_14") (pintype "passive"))
    )
    (net (code "134") (name "Net-(SW13-S3)") (class "Default")
      (node (ref "R158") (pin "1") (pintype "passive"))
      (node (ref "SW13") (pin "11") (pinfunction "S3_11") (pintype "passive"))
    )
    (net (code "135") (name "Net-(SW13-S4)") (class "Default")
      (node (ref "R162") (pin "1") (pintype "passive"))
      (node (ref "SW13") (pin "6") (pinfunction "S4_6") (pintype "passive"))
    )
    (net (code "136") (name "Net-(SW14-S2)") (class "Default")
      (node (ref "R155") (pin "1") (pintype "passive"))
      (node (ref "SW14") (pin "14") (pinfunction "S2_14") (pintype "passive"))
    )
    (net (code "137") (name "Net-(SW14-S3)") (class "Default")
      (node (ref "R159") (pin "1") (pintype "passive"))
      (node (ref "SW14") (pin "11") (pinfunction "S3_11") (pintype "passive"))
    )
    (net (code "138") (name "Net-(SW14-S4)") (class "Default")
      (node (ref "R163") (pin "1") (pintype "passive"))
      (node (ref "SW14") (pin "6") (pinfunction "S4_6") (pintype "passive"))
    )
    (net (code "139") (name "Net-(SW22-S2)") (class "Default")
      (node (ref "R247") (pin "1") (pintype "passive"))
      (node (ref "SW22") (pin "14") (pinfunction "S2_14") (pintype "passive"))
    )
    (net (code "140") (name "Net-(SW22-S3)") (class "Default")
      (node (ref "R248") (pin "1") (pintype "passive"))
      (node (ref "SW22") (pin "11") (pinfunction "S3_11") (pintype "passive"))
    )
    (net (code "141") (name "Net-(SW22-S4)") (class "Default")
      (node (ref "R249") (pin "1") (pintype "passive"))
      (node (ref "SW22") (pin "6") (pinfunction "S4_6") (pintype "passive"))
    )
    (net (code "142") (name "Net-(SW24-S2)") (class "Default")
      (node (ref "R365") (pin "1") (pintype "passive"))
      (node (ref "SW24") (pin "14") (pinfunction "S2_14") (pintype "passive"))
    )
    (net (code "143") (name "Net-(SW24-S3)") (class "Default")
      (node (ref "R366") (pin "1") (pintype "passive"))
      (node (ref "SW24") (pin "11") (pinfunction "S3_11") (pintype "passive"))
    )
    (net (code "144") (name "Net-(SW24-S4)") (class "Default")
      (node (ref "R367") (pin "1") (pintype "passive"))
      (node (ref "SW24") (pin "6") (pinfunction "S4_6") (pintype "passive"))
    )
  )
)
